# OpticalBoardRev1.net
KiCad netlist of a schematic drawn in EAGLE
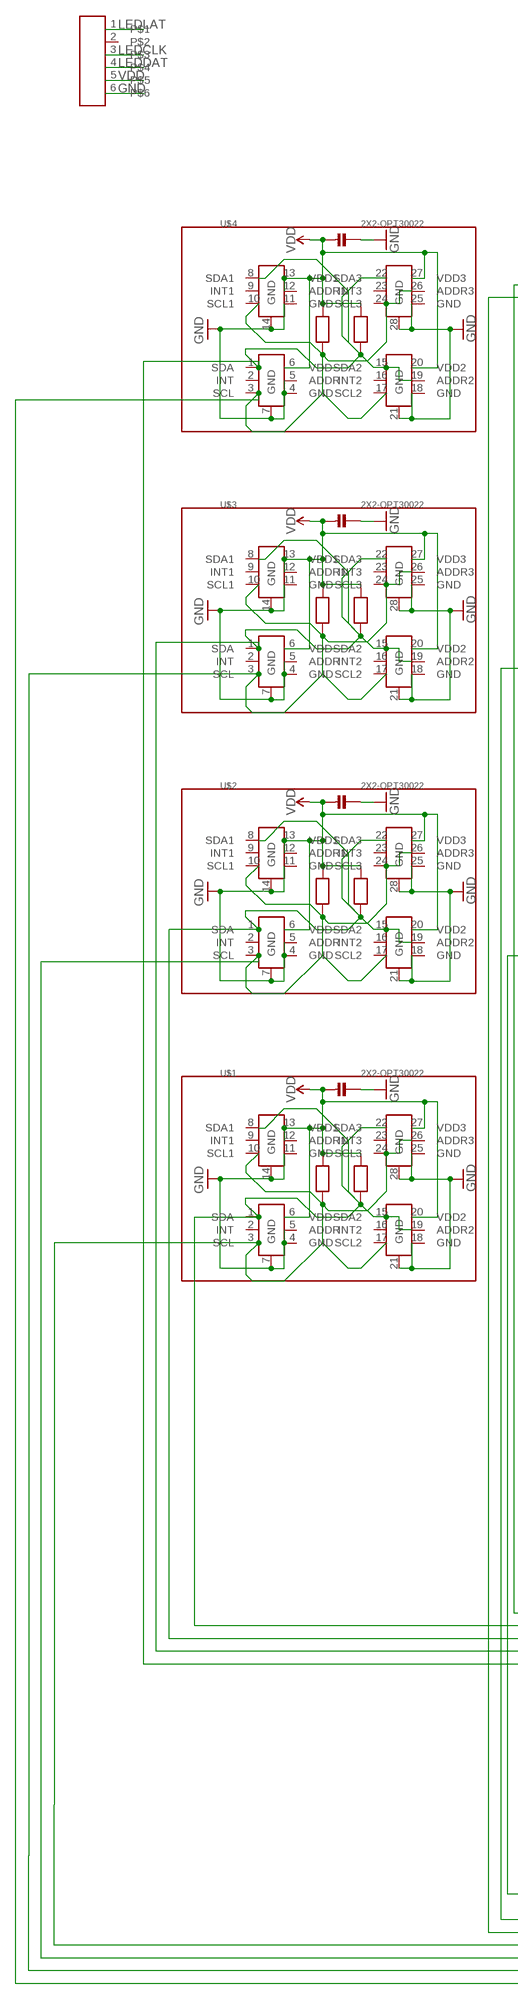
[diagram p0: schematic, sheet 1, part 1 of 2]
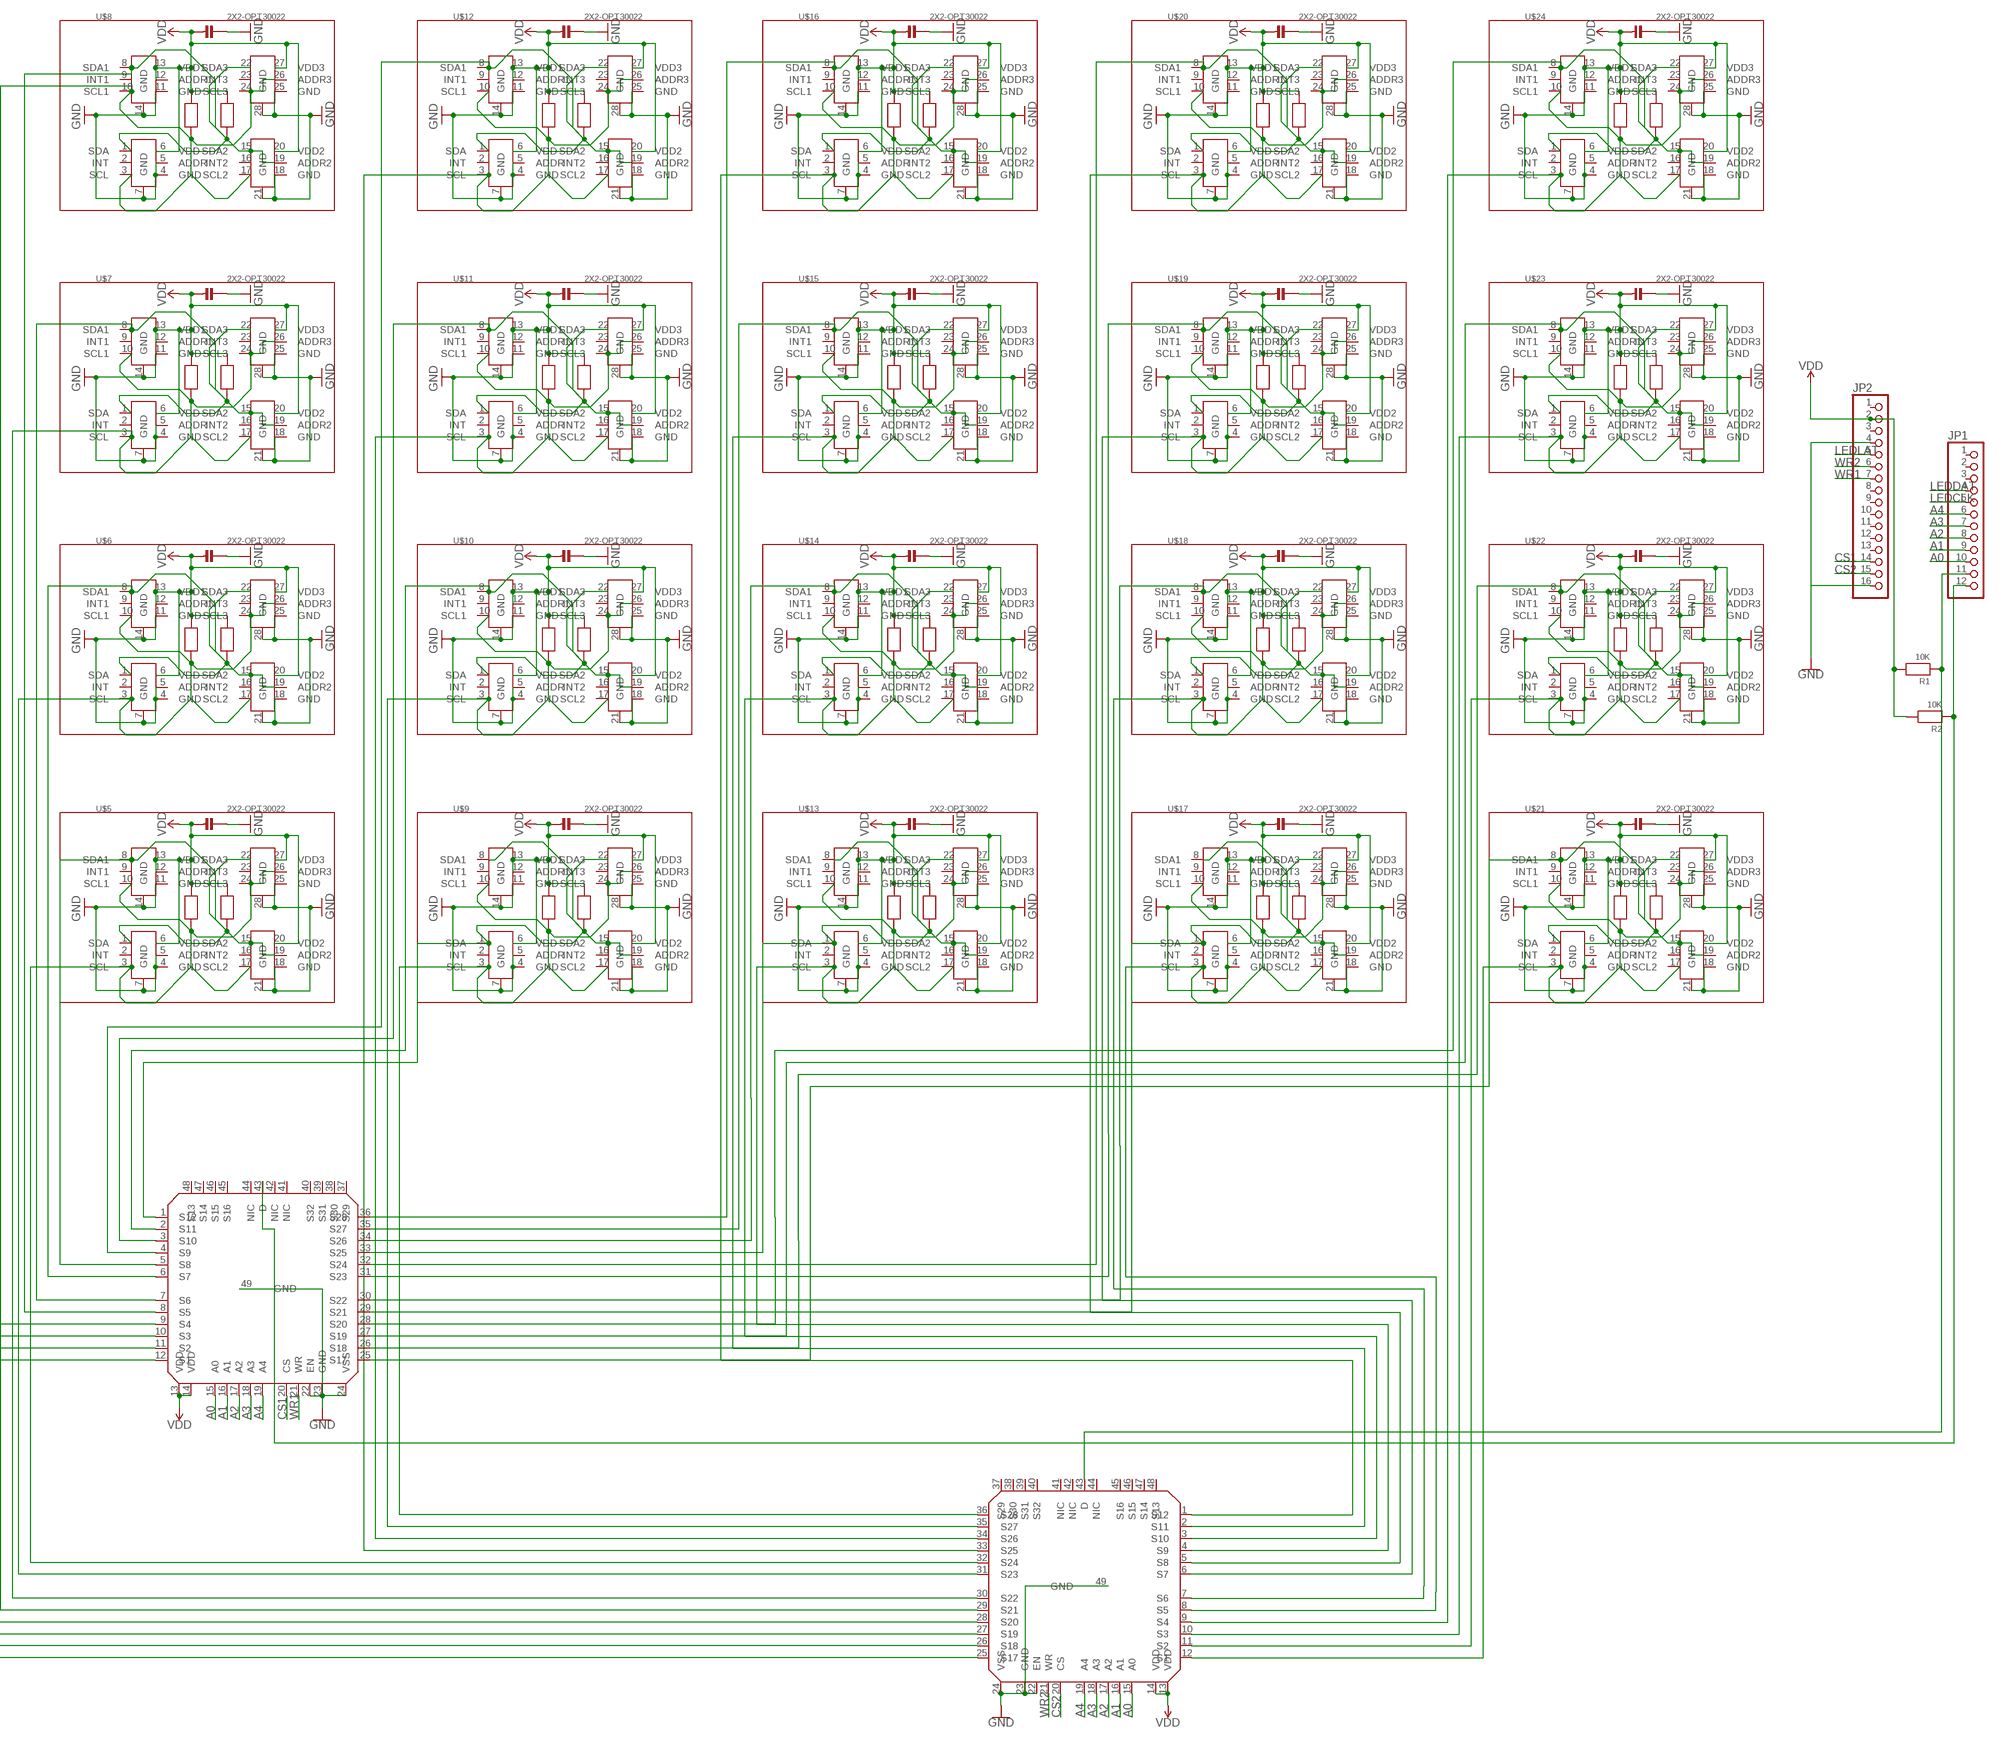
[diagram p1: schematic, sheet 1, part 2 of 2]

(export (version "E")
  (design (tool "Eeschema 10.0.6"))
  (components
    (comp (ref "JP1")
      (value "HEADER-1X12")
      (footprint "eagle-import:1X12_ROUND")
      (libsource (lib "eagle-import") (part "HEADER-1X12"))
    )
    (comp (ref "JP2")
      (value "HEADER-1X16ROUND")
      (footprint "eagle-import:1X16_ROUND")
      (libsource (lib "eagle-import") (part "HEADER-1X16ROUND"))
    )
    (comp (ref "R1")
      (value "10K")
      (footprint "eagle-import:_0805")
      (libsource (lib "eagle-import") (part "RESISTOR_0805"))
    )
    (comp (ref "R2")
      (value "10K")
      (footprint "eagle-import:_0805")
      (libsource (lib "eagle-import") (part "RESISTOR_0805"))
    )
    (comp (ref "U$1")
      (value "2X2-OPT30022")
      (footprint "eagle-import:2X2-OPT3002-2")
      (libsource (lib "eagle-import") (part "2X2-OPT30022"))
    )
    (comp (ref "U$2")
      (value "2X2-OPT30022")
      (footprint "eagle-import:2X2-OPT3002-2")
      (libsource (lib "eagle-import") (part "2X2-OPT30022"))
    )
    (comp (ref "U$3")
      (value "2X2-OPT30022")
      (footprint "eagle-import:2X2-OPT3002-2")
      (libsource (lib "eagle-import") (part "2X2-OPT30022"))
    )
    (comp (ref "U$4")
      (value "2X2-OPT30022")
      (footprint "eagle-import:2X2-OPT3002-2")
      (libsource (lib "eagle-import") (part "2X2-OPT30022"))
    )
    (comp (ref "U$5")
      (value "2X2-OPT30022")
      (footprint "eagle-import:2X2-OPT3002-2")
      (libsource (lib "eagle-import") (part "2X2-OPT30022"))
    )
    (comp (ref "U$6")
      (value "2X2-OPT30022")
      (footprint "eagle-import:2X2-OPT3002-2")
      (libsource (lib "eagle-import") (part "2X2-OPT30022"))
    )
    (comp (ref "U$7")
      (value "2X2-OPT30022")
      (footprint "eagle-import:2X2-OPT3002-2")
      (libsource (lib "eagle-import") (part "2X2-OPT30022"))
    )
    (comp (ref "U$8")
      (value "2X2-OPT30022")
      (footprint "eagle-import:2X2-OPT3002-2")
      (libsource (lib "eagle-import") (part "2X2-OPT30022"))
    )
    (comp (ref "U$9")
      (value "2X2-OPT30022")
      (footprint "eagle-import:2X2-OPT3002-2")
      (libsource (lib "eagle-import") (part "2X2-OPT30022"))
    )
    (comp (ref "U$10")
      (value "2X2-OPT30022")
      (footprint "eagle-import:2X2-OPT3002-2")
      (libsource (lib "eagle-import") (part "2X2-OPT30022"))
    )
    (comp (ref "U$11")
      (value "2X2-OPT30022")
      (footprint "eagle-import:2X2-OPT3002-2")
      (libsource (lib "eagle-import") (part "2X2-OPT30022"))
    )
    (comp (ref "U$12")
      (value "2X2-OPT30022")
      (footprint "eagle-import:2X2-OPT3002-2")
      (libsource (lib "eagle-import") (part "2X2-OPT30022"))
    )
    (comp (ref "U$13")
      (value "2X2-OPT30022")
      (footprint "eagle-import:2X2-OPT3002-2")
      (libsource (lib "eagle-import") (part "2X2-OPT30022"))
    )
    (comp (ref "U$14")
      (value "2X2-OPT30022")
      (footprint "eagle-import:2X2-OPT3002-2")
      (libsource (lib "eagle-import") (part "2X2-OPT30022"))
    )
    (comp (ref "U$15")
      (value "2X2-OPT30022")
      (footprint "eagle-import:2X2-OPT3002-2")
      (libsource (lib "eagle-import") (part "2X2-OPT30022"))
    )
    (comp (ref "U$16")
      (value "2X2-OPT30022")
      (footprint "eagle-import:2X2-OPT3002-2")
      (libsource (lib "eagle-import") (part "2X2-OPT30022"))
    )
    (comp (ref "U$17")
      (value "2X2-OPT30022")
      (footprint "eagle-import:2X2-OPT3002-2")
      (libsource (lib "eagle-import") (part "2X2-OPT30022"))
    )
    (comp (ref "U$18")
      (value "2X2-OPT30022")
      (footprint "eagle-import:2X2-OPT3002-2")
      (libsource (lib "eagle-import") (part "2X2-OPT30022"))
    )
    (comp (ref "U$19")
      (value "2X2-OPT30022")
      (footprint "eagle-import:2X2-OPT3002-2")
      (libsource (lib "eagle-import") (part "2X2-OPT30022"))
    )
    (comp (ref "U$20")
      (value "2X2-OPT30022")
      (footprint "eagle-import:2X2-OPT3002-2")
      (libsource (lib "eagle-import") (part "2X2-OPT30022"))
    )
    (comp (ref "U$21")
      (value "2X2-OPT30022")
      (footprint "eagle-import:2X2-OPT3002-2")
      (libsource (lib "eagle-import") (part "2X2-OPT30022"))
    )
    (comp (ref "U$22")
      (value "2X2-OPT30022")
      (footprint "eagle-import:2X2-OPT3002-2")
      (libsource (lib "eagle-import") (part "2X2-OPT30022"))
    )
    (comp (ref "U$23")
      (value "2X2-OPT30022")
      (footprint "eagle-import:2X2-OPT3002-2")
      (libsource (lib "eagle-import") (part "2X2-OPT30022"))
    )
    (comp (ref "U$24")
      (value "2X2-OPT30022")
      (footprint "eagle-import:2X2-OPT3002-2")
      (libsource (lib "eagle-import") (part "2X2-OPT30022"))
    )
    (comp (ref "U$25")
      (value "CONNECTOR_6PIN")
      (footprint "eagle-import:CONNECTOR_6PIN")
      (libsource (lib "eagle-import") (part "CONNECTOR_6PIN"))
    )
    (comp (ref "U$26")
      (value "32MUXTOP")
      (footprint "eagle-import:32MUX")
      (libsource (lib "eagle-import") (part "32MUXTOP"))
    )
    (comp (ref "U$27")
      (value "32MUXBOT")
      (footprint "eagle-import:32MUX_BOT")
      (libsource (lib "eagle-import") (part "32MUXBOT"))
    )
  )
  (nets
    (net (code "1") (name "/A0") (class "Default")
      (node (ref "JP1") (pin "10") (pinfunction "10_10") (pintype "passive"))
      (node (ref "U$26") (pin "15") (pinfunction "A0_15") (pintype "bidirectional"))
      (node (ref "U$27") (pin "15") (pinfunction "A0_15") (pintype "bidirectional"))
    )
    (net (code "2") (name "/A1") (class "Default")
      (node (ref "JP1") (pin "9") (pinfunction "9_9") (pintype "passive"))
      (node (ref "U$26") (pin "16") (pinfunction "A1_16") (pintype "bidirectional"))
      (node (ref "U$27") (pin "16") (pinfunction "A1_16") (pintype "bidirectional"))
    )
    (net (code "3") (name "/A2") (class "Default")
      (node (ref "JP1") (pin "8") (pinfunction "8_8") (pintype "passive"))
      (node (ref "U$26") (pin "17") (pinfunction "A2_17") (pintype "bidirectional"))
      (node (ref "U$27") (pin "17") (pinfunction "A2_17") (pintype "bidirectional"))
    )
    (net (code "4") (name "/A3") (class "Default")
      (node (ref "JP1") (pin "7") (pinfunction "7_7") (pintype "passive"))
      (node (ref "U$26") (pin "18") (pinfunction "A3_18") (pintype "bidirectional"))
      (node (ref "U$27") (pin "18") (pinfunction "A3_18") (pintype "bidirectional"))
    )
    (net (code "5") (name "/A4") (class "Default")
      (node (ref "JP1") (pin "6") (pinfunction "6_6") (pintype "passive"))
      (node (ref "U$26") (pin "19") (pinfunction "A4_19") (pintype "bidirectional"))
      (node (ref "U$27") (pin "19") (pinfunction "A4_19") (pintype "bidirectional"))
    )
    (net (code "6") (name "/CS1") (class "Default")
      (node (ref "JP2") (pin "14") (pinfunction "14_14") (pintype "passive"))
      (node (ref "U$26") (pin "20") (pinfunction "CS_20") (pintype "bidirectional"))
    )
    (net (code "7") (name "/CS2") (class "Default")
      (node (ref "JP2") (pin "15") (pinfunction "15_15") (pintype "passive"))
      (node (ref "U$27") (pin "20") (pinfunction "CS_20") (pintype "bidirectional"))
    )
    (net (code "8") (name "/LEDCLK") (class "Default")
      (node (ref "JP1") (pin "5") (pinfunction "5_5") (pintype "passive"))
      (node (ref "U$25") (pin "3") (pinfunction "P$3_3") (pintype "bidirectional"))
    )
    (net (code "9") (name "/LEDDAT") (class "Default")
      (node (ref "JP1") (pin "4") (pinfunction "4_4") (pintype "passive"))
      (node (ref "U$25") (pin "4") (pinfunction "P$4_4") (pintype "bidirectional"))
    )
    (net (code "10") (name "/LEDLAT") (class "Default")
      (node (ref "JP2") (pin "5") (pinfunction "5_5") (pintype "passive"))
      (node (ref "U$25") (pin "1") (pinfunction "P$1_1") (pintype "bidirectional"))
    )
    (net (code "11") (name "/WR1") (class "Default")
      (node (ref "JP2") (pin "7") (pinfunction "7_7") (pintype "passive"))
      (node (ref "U$26") (pin "21") (pinfunction "WR_21") (pintype "bidirectional"))
    )
    (net (code "12") (name "/WR2") (class "Default")
      (node (ref "JP2") (pin "6") (pinfunction "6_6") (pintype "passive"))
      (node (ref "U$27") (pin "21") (pinfunction "WR_21") (pintype "bidirectional"))
    )
    (net (code "13") (name "GND") (class "Default")
      (node (ref "JP2") (pin "16") (pinfunction "16_16") (pintype "passive"))
      (node (ref "JP2") (pin "4") (pinfunction "4_4") (pintype "passive"))
      (node (ref "U$1") (pin "11") (pinfunction "GND_11") (pintype "bidirectional"))
      (node (ref "U$1") (pin "14") (pinfunction "GND_14") (pintype "bidirectional"))
      (node (ref "U$1") (pin "18") (pinfunction "GND_18") (pintype "bidirectional"))
      (node (ref "U$1") (pin "21") (pinfunction "GND_21") (pintype "bidirectional"))
      (node (ref "U$1") (pin "25") (pinfunction "GND_25") (pintype "bidirectional"))
      (node (ref "U$1") (pin "28") (pinfunction "GND_28") (pintype "bidirectional"))
      (node (ref "U$1") (pin "30") (pinfunction "GND_30") (pintype "passive"))
      (node (ref "U$1") (pin "4") (pinfunction "GND_4") (pintype "bidirectional"))
      (node (ref "U$1") (pin "5") (pinfunction "ADDR_5") (pintype "bidirectional"))
      (node (ref "U$1") (pin "7") (pinfunction "GND_7") (pintype "bidirectional"))
      (node (ref "U$10") (pin "11") (pinfunction "GND_11") (pintype "bidirectional"))
      (node (ref "U$10") (pin "14") (pinfunction "GND_14") (pintype "bidirectional"))
      (node (ref "U$10") (pin "18") (pinfunction "GND_18") (pintype "bidirectional"))
      (node (ref "U$10") (pin "21") (pinfunction "GND_21") (pintype "bidirectional"))
      (node (ref "U$10") (pin "25") (pinfunction "GND_25") (pintype "bidirectional"))
      (node (ref "U$10") (pin "28") (pinfunction "GND_28") (pintype "bidirectional"))
      (node (ref "U$10") (pin "30") (pinfunction "GND_30") (pintype "passive"))
      (node (ref "U$10") (pin "4") (pinfunction "GND_4") (pintype "bidirectional"))
      (node (ref "U$10") (pin "5") (pinfunction "ADDR_5") (pintype "bidirectional"))
      (node (ref "U$10") (pin "7") (pinfunction "GND_7") (pintype "bidirectional"))
      (node (ref "U$11") (pin "11") (pinfunction "GND_11") (pintype "bidirectional"))
      (node (ref "U$11") (pin "14") (pinfunction "GND_14") (pintype "bidirectional"))
      (node (ref "U$11") (pin "18") (pinfunction "GND_18") (pintype "bidirectional"))
      (node (ref "U$11") (pin "21") (pinfunction "GND_21") (pintype "bidirectional"))
      (node (ref "U$11") (pin "25") (pinfunction "GND_25") (pintype "bidirectional"))
      (node (ref "U$11") (pin "28") (pinfunction "GND_28") (pintype "bidirectional"))
      (node (ref "U$11") (pin "30") (pinfunction "GND_30") (pintype "passive"))
      (node (ref "U$11") (pin "4") (pinfunction "GND_4") (pintype "bidirectional"))
      (node (ref "U$11") (pin "5") (pinfunction "ADDR_5") (pintype "bidirectional"))
      (node (ref "U$11") (pin "7") (pinfunction "GND_7") (pintype "bidirectional"))
      (node (ref "U$12") (pin "11") (pinfunction "GND_11") (pintype "bidirectional"))
      (node (ref "U$12") (pin "14") (pinfunction "GND_14") (pintype "bidirectional"))
      (node (ref "U$12") (pin "18") (pinfunction "GND_18") (pintype "bidirectional"))
      (node (ref "U$12") (pin "21") (pinfunction "GND_21") (pintype "bidirectional"))
      (node (ref "U$12") (pin "25") (pinfunction "GND_25") (pintype "bidirectional"))
      (node (ref "U$12") (pin "28") (pinfunction "GND_28") (pintype "bidirectional"))
      (node (ref "U$12") (pin "30") (pinfunction "GND_30") (pintype "passive"))
      (node (ref "U$12") (pin "4") (pinfunction "GND_4") (pintype "bidirectional"))
      (node (ref "U$12") (pin "5") (pinfunction "ADDR_5") (pintype "bidirectional"))
      (node (ref "U$12") (pin "7") (pinfunction "GND_7") (pintype "bidirectional"))
      (node (ref "U$13") (pin "11") (pinfunction "GND_11") (pintype "bidirectional"))
      (node (ref "U$13") (pin "14") (pinfunction "GND_14") (pintype "bidirectional"))
      (node (ref "U$13") (pin "18") (pinfunction "GND_18") (pintype "bidirectional"))
      (node (ref "U$13") (pin "21") (pinfunction "GND_21") (pintype "bidirectional"))
      (node (ref "U$13") (pin "25") (pinfunction "GND_25") (pintype "bidirectional"))
      (node (ref "U$13") (pin "28") (pinfunction "GND_28") (pintype "bidirectional"))
      (node (ref "U$13") (pin "30") (pinfunction "GND_30") (pintype "passive"))
      (node (ref "U$13") (pin "4") (pinfunction "GND_4") (pintype "bidirectional"))
      (node (ref "U$13") (pin "5") (pinfunction "ADDR_5") (pintype "bidirectional"))
      (node (ref "U$13") (pin "7") (pinfunction "GND_7") (pintype "bidirectional"))
      (node (ref "U$14") (pin "11") (pinfunction "GND_11") (pintype "bidirectional"))
      (node (ref "U$14") (pin "14") (pinfunction "GND_14") (pintype "bidirectional"))
      (node (ref "U$14") (pin "18") (pinfunction "GND_18") (pintype "bidirectional"))
      (node (ref "U$14") (pin "21") (pinfunction "GND_21") (pintype "bidirectional"))
      (node (ref "U$14") (pin "25") (pinfunction "GND_25") (pintype "bidirectional"))
      (node (ref "U$14") (pin "28") (pinfunction "GND_28") (pintype "bidirectional"))
      (node (ref "U$14") (pin "30") (pinfunction "GND_30") (pintype "passive"))
      (node (ref "U$14") (pin "4") (pinfunction "GND_4") (pintype "bidirectional"))
      (node (ref "U$14") (pin "5") (pinfunction "ADDR_5") (pintype "bidirectional"))
      (node (ref "U$14") (pin "7") (pinfunction "GND_7") (pintype "bidirectional"))
      (node (ref "U$15") (pin "11") (pinfunction "GND_11") (pintype "bidirectional"))
      (node (ref "U$15") (pin "14") (pinfunction "GND_14") (pintype "bidirectional"))
      (node (ref "U$15") (pin "18") (pinfunction "GND_18") (pintype "bidirectional"))
      (node (ref "U$15") (pin "21") (pinfunction "GND_21") (pintype "bidirectional"))
      (node (ref "U$15") (pin "25") (pinfunction "GND_25") (pintype "bidirectional"))
      (node (ref "U$15") (pin "28") (pinfunction "GND_28") (pintype "bidirectional"))
      (node (ref "U$15") (pin "30") (pinfunction "GND_30") (pintype "passive"))
      (node (ref "U$15") (pin "4") (pinfunction "GND_4") (pintype "bidirectional"))
      (node (ref "U$15") (pin "5") (pinfunction "ADDR_5") (pintype "bidirectional"))
      (node (ref "U$15") (pin "7") (pinfunction "GND_7") (pintype "bidirectional"))
      (node (ref "U$16") (pin "11") (pinfunction "GND_11") (pintype "bidirectional"))
      (node (ref "U$16") (pin "14") (pinfunction "GND_14") (pintype "bidirectional"))
      (node (ref "U$16") (pin "18") (pinfunction "GND_18") (pintype "bidirectional"))
      (node (ref "U$16") (pin "21") (pinfunction "GND_21") (pintype "bidirectional"))
      (node (ref "U$16") (pin "25") (pinfunction "GND_25") (pintype "bidirectional"))
      (node (ref "U$16") (pin "28") (pinfunction "GND_28") (pintype "bidirectional"))
      (node (ref "U$16") (pin "30") (pinfunction "GND_30") (pintype "passive"))
      (node (ref "U$16") (pin "4") (pinfunction "GND_4") (pintype "bidirectional"))
      (node (ref "U$16") (pin "5") (pinfunction "ADDR_5") (pintype "bidirectional"))
      (node (ref "U$16") (pin "7") (pinfunction "GND_7") (pintype "bidirectional"))
      (node (ref "U$17") (pin "11") (pinfunction "GND_11") (pintype "bidirectional"))
      (node (ref "U$17") (pin "14") (pinfunction "GND_14") (pintype "bidirectional"))
      (node (ref "U$17") (pin "18") (pinfunction "GND_18") (pintype "bidirectional"))
      (node (ref "U$17") (pin "21") (pinfunction "GND_21") (pintype "bidirectional"))
      (node (ref "U$17") (pin "25") (pinfunction "GND_25") (pintype "bidirectional"))
      (node (ref "U$17") (pin "28") (pinfunction "GND_28") (pintype "bidirectional"))
      (node (ref "U$17") (pin "30") (pinfunction "GND_30") (pintype "passive"))
      (node (ref "U$17") (pin "4") (pinfunction "GND_4") (pintype "bidirectional"))
      (node (ref "U$17") (pin "5") (pinfunction "ADDR_5") (pintype "bidirectional"))
      (node (ref "U$17") (pin "7") (pinfunction "GND_7") (pintype "bidirectional"))
      (node (ref "U$18") (pin "11") (pinfunction "GND_11") (pintype "bidirectional"))
      (node (ref "U$18") (pin "14") (pinfunction "GND_14") (pintype "bidirectional"))
      (node (ref "U$18") (pin "18") (pinfunction "GND_18") (pintype "bidirectional"))
      (node (ref "U$18") (pin "21") (pinfunction "GND_21") (pintype "bidirectional"))
      (node (ref "U$18") (pin "25") (pinfunction "GND_25") (pintype "bidirectional"))
      (node (ref "U$18") (pin "28") (pinfunction "GND_28") (pintype "bidirectional"))
      (node (ref "U$18") (pin "30") (pinfunction "GND_30") (pintype "passive"))
      (node (ref "U$18") (pin "4") (pinfunction "GND_4") (pintype "bidirectional"))
      (node (ref "U$18") (pin "5") (pinfunction "ADDR_5") (pintype "bidirectional"))
      (node (ref "U$18") (pin "7") (pinfunction "GND_7") (pintype "bidirectional"))
      (node (ref "U$19") (pin "11") (pinfunction "GND_11") (pintype "bidirectional"))
      (node (ref "U$19") (pin "14") (pinfunction "GND_14") (pintype "bidirectional"))
      (node (ref "U$19") (pin "18") (pinfunction "GND_18") (pintype "bidirectional"))
      (node (ref "U$19") (pin "21") (pinfunction "GND_21") (pintype "bidirectional"))
      (node (ref "U$19") (pin "25") (pinfunction "GND_25") (pintype "bidirectional"))
      (node (ref "U$19") (pin "28") (pinfunction "GND_28") (pintype "bidirectional"))
      (node (ref "U$19") (pin "30") (pinfunction "GND_30") (pintype "passive"))
      (node (ref "U$19") (pin "4") (pinfunction "GND_4") (pintype "bidirectional"))
      (node (ref "U$19") (pin "5") (pinfunction "ADDR_5") (pintype "bidirectional"))
      (node (ref "U$19") (pin "7") (pinfunction "GND_7") (pintype "bidirectional"))
      (node (ref "U$2") (pin "11") (pinfunction "GND_11") (pintype "bidirectional"))
      (node (ref "U$2") (pin "14") (pinfunction "GND_14") (pintype "bidirectional"))
      (node (ref "U$2") (pin "18") (pinfunction "GND_18") (pintype "bidirectional"))
      (node (ref "U$2") (pin "21") (pinfunction "GND_21") (pintype "bidirectional"))
      (node (ref "U$2") (pin "25") (pinfunction "GND_25") (pintype "bidirectional"))
      (node (ref "U$2") (pin "28") (pinfunction "GND_28") (pintype "bidirectional"))
      (node (ref "U$2") (pin "30") (pinfunction "GND_30") (pintype "passive"))
      (node (ref "U$2") (pin "4") (pinfunction "GND_4") (pintype "bidirectional"))
      (node (ref "U$2") (pin "5") (pinfunction "ADDR_5") (pintype "bidirectional"))
      (node (ref "U$2") (pin "7") (pinfunction "GND_7") (pintype "bidirectional"))
      (node (ref "U$20") (pin "11") (pinfunction "GND_11") (pintype "bidirectional"))
      (node (ref "U$20") (pin "14") (pinfunction "GND_14") (pintype "bidirectional"))
      (node (ref "U$20") (pin "18") (pinfunction "GND_18") (pintype "bidirectional"))
      (node (ref "U$20") (pin "21") (pinfunction "GND_21") (pintype "bidirectional"))
      (node (ref "U$20") (pin "25") (pinfunction "GND_25") (pintype "bidirectional"))
      (node (ref "U$20") (pin "28") (pinfunction "GND_28") (pintype "bidirectional"))
      (node (ref "U$20") (pin "30") (pinfunction "GND_30") (pintype "passive"))
      (node (ref "U$20") (pin "4") (pinfunction "GND_4") (pintype "bidirectional"))
      (node (ref "U$20") (pin "5") (pinfunction "ADDR_5") (pintype "bidirectional"))
      (node (ref "U$20") (pin "7") (pinfunction "GND_7") (pintype "bidirectional"))
      (node (ref "U$21") (pin "11") (pinfunction "GND_11") (pintype "bidirectional"))
      (node (ref "U$21") (pin "14") (pinfunction "GND_14") (pintype "bidirectional"))
      (node (ref "U$21") (pin "18") (pinfunction "GND_18") (pintype "bidirectional"))
      (node (ref "U$21") (pin "21") (pinfunction "GND_21") (pintype "bidirectional"))
      (node (ref "U$21") (pin "25") (pinfunction "GND_25") (pintype "bidirectional"))
      (node (ref "U$21") (pin "28") (pinfunction "GND_28") (pintype "bidirectional"))
      (node (ref "U$21") (pin "30") (pinfunction "GND_30") (pintype "passive"))
      (node (ref "U$21") (pin "4") (pinfunction "GND_4") (pintype "bidirectional"))
      (node (ref "U$21") (pin "5") (pinfunction "ADDR_5") (pintype "bidirectional"))
      (node (ref "U$21") (pin "7") (pinfunction "GND_7") (pintype "bidirectional"))
      (node (ref "U$22") (pin "11") (pinfunction "GND_11") (pintype "bidirectional"))
      (node (ref "U$22") (pin "14") (pinfunction "GND_14") (pintype "bidirectional"))
      (node (ref "U$22") (pin "18") (pinfunction "GND_18") (pintype "bidirectional"))
      (node (ref "U$22") (pin "21") (pinfunction "GND_21") (pintype "bidirectional"))
      (node (ref "U$22") (pin "25") (pinfunction "GND_25") (pintype "bidirectional"))
      (node (ref "U$22") (pin "28") (pinfunction "GND_28") (pintype "bidirectional"))
      (node (ref "U$22") (pin "30") (pinfunction "GND_30") (pintype "passive"))
      (node (ref "U$22") (pin "4") (pinfunction "GND_4") (pintype "bidirectional"))
      (node (ref "U$22") (pin "5") (pinfunction "ADDR_5") (pintype "bidirectional"))
      (node (ref "U$22") (pin "7") (pinfunction "GND_7") (pintype "bidirectional"))
      (node (ref "U$23") (pin "11") (pinfunction "GND_11") (pintype "bidirectional"))
      (node (ref "U$23") (pin "14") (pinfunction "GND_14") (pintype "bidirectional"))
      (node (ref "U$23") (pin "18") (pinfunction "GND_18") (pintype "bidirectional"))
      (node (ref "U$23") (pin "21") (pinfunction "GND_21") (pintype "bidirectional"))
      (node (ref "U$23") (pin "25") (pinfunction "GND_25") (pintype "bidirectional"))
      (node (ref "U$23") (pin "28") (pinfunction "GND_28") (pintype "bidirectional"))
      (node (ref "U$23") (pin "30") (pinfunction "GND_30") (pintype "passive"))
      (node (ref "U$23") (pin "4") (pinfunction "GND_4") (pintype "bidirectional"))
      (node (ref "U$23") (pin "5") (pinfunction "ADDR_5") (pintype "bidirectional"))
      (node (ref "U$23") (pin "7") (pinfunction "GND_7") (pintype "bidirectional"))
      (node (ref "U$24") (pin "11") (pinfunction "GND_11") (pintype "bidirectional"))
      (node (ref "U$24") (pin "14") (pinfunction "GND_14") (pintype "bidirectional"))
      (node (ref "U$24") (pin "18") (pinfunction "GND_18") (pintype "bidirectional"))
      (node (ref "U$24") (pin "21") (pinfunction "GND_21") (pintype "bidirectional"))
      (node (ref "U$24") (pin "25") (pinfunction "GND_25") (pintype "bidirectional"))
      (node (ref "U$24") (pin "28") (pinfunction "GND_28") (pintype "bidirectional"))
      (node (ref "U$24") (pin "30") (pinfunction "GND_30") (pintype "passive"))
      (node (ref "U$24") (pin "4") (pinfunction "GND_4") (pintype "bidirectional"))
      (node (ref "U$24") (pin "5") (pinfunction "ADDR_5") (pintype "bidirectional"))
      (node (ref "U$24") (pin "7") (pinfunction "GND_7") (pintype "bidirectional"))
      (node (ref "U$25") (pin "6") (pinfunction "P$6_6") (pintype "bidirectional"))
      (node (ref "U$26") (pin "22") (pinfunction "EN_22") (pintype "bidirectional"))
      (node (ref "U$26") (pin "23") (pinfunction "GND_23") (pintype "bidirectional"))
      (node (ref "U$26") (pin "24") (pinfunction "VSS_24") (pintype "bidirectional"))
      (node (ref "U$26") (pin "49") (pinfunction "GND_49") (pintype "bidirectional"))
      (node (ref "U$27") (pin "22") (pinfunction "EN_22") (pintype "bidirectional"))
      (node (ref "U$27") (pin "23") (pinfunction "GND_23") (pintype "bidirectional"))
      (node (ref "U$27") (pin "24") (pinfunction "VSS_24") (pintype "bidirectional"))
      (node (ref "U$27") (pin "49") (pinfunction "GND_49") (pintype "bidirectional"))
      (node (ref "U$3") (pin "11") (pinfunction "GND_11") (pintype "bidirectional"))
      (node (ref "U$3") (pin "14") (pinfunction "GND_14") (pintype "bidirectional"))
      (node (ref "U$3") (pin "18") (pinfunction "GND_18") (pintype "bidirectional"))
      (node (ref "U$3") (pin "21") (pinfunction "GND_21") (pintype "bidirectional"))
      (node (ref "U$3") (pin "25") (pinfunction "GND_25") (pintype "bidirectional"))
      (node (ref "U$3") (pin "28") (pinfunction "GND_28") (pintype "bidirectional"))
      (node (ref "U$3") (pin "30") (pinfunction "GND_30") (pintype "passive"))
      (node (ref "U$3") (pin "4") (pinfunction "GND_4") (pintype "bidirectional"))
      (node (ref "U$3") (pin "5") (pinfunction "ADDR_5") (pintype "bidirectional"))
      (node (ref "U$3") (pin "7") (pinfunction "GND_7") (pintype "bidirectional"))
      (node (ref "U$4") (pin "11") (pinfunction "GND_11") (pintype "bidirectional"))
      (node (ref "U$4") (pin "14") (pinfunction "GND_14") (pintype "bidirectional"))
      (node (ref "U$4") (pin "18") (pinfunction "GND_18") (pintype "bidirectional"))
      (node (ref "U$4") (pin "21") (pinfunction "GND_21") (pintype "bidirectional"))
      (node (ref "U$4") (pin "25") (pinfunction "GND_25") (pintype "bidirectional"))
      (node (ref "U$4") (pin "28") (pinfunction "GND_28") (pintype "bidirectional"))
      (node (ref "U$4") (pin "30") (pinfunction "GND_30") (pintype "passive"))
      (node (ref "U$4") (pin "4") (pinfunction "GND_4") (pintype "bidirectional"))
      (node (ref "U$4") (pin "5") (pinfunction "ADDR_5") (pintype "bidirectional"))
      (node (ref "U$4") (pin "7") (pinfunction "GND_7") (pintype "bidirectional"))
      (node (ref "U$5") (pin "11") (pinfunction "GND_11") (pintype "bidirectional"))
      (node (ref "U$5") (pin "14") (pinfunction "GND_14") (pintype "bidirectional"))
      (node (ref "U$5") (pin "18") (pinfunction "GND_18") (pintype "bidirectional"))
      (node (ref "U$5") (pin "21") (pinfunction "GND_21") (pintype "bidirectional"))
      (node (ref "U$5") (pin "25") (pinfunction "GND_25") (pintype "bidirectional"))
      (node (ref "U$5") (pin "28") (pinfunction "GND_28") (pintype "bidirectional"))
      (node (ref "U$5") (pin "30") (pinfunction "GND_30") (pintype "passive"))
      (node (ref "U$5") (pin "4") (pinfunction "GND_4") (pintype "bidirectional"))
      (node (ref "U$5") (pin "5") (pinfunction "ADDR_5") (pintype "bidirectional"))
      (node (ref "U$5") (pin "7") (pinfunction "GND_7") (pintype "bidirectional"))
      (node (ref "U$6") (pin "11") (pinfunction "GND_11") (pintype "bidirectional"))
      (node (ref "U$6") (pin "14") (pinfunction "GND_14") (pintype "bidirectional"))
      (node (ref "U$6") (pin "18") (pinfunction "GND_18") (pintype "bidirectional"))
      (node (ref "U$6") (pin "21") (pinfunction "GND_21") (pintype "bidirectional"))
      (node (ref "U$6") (pin "25") (pinfunction "GND_25") (pintype "bidirectional"))
      (node (ref "U$6") (pin "28") (pinfunction "GND_28") (pintype "bidirectional"))
      (node (ref "U$6") (pin "30") (pinfunction "GND_30") (pintype "passive"))
      (node (ref "U$6") (pin "4") (pinfunction "GND_4") (pintype "bidirectional"))
      (node (ref "U$6") (pin "5") (pinfunction "ADDR_5") (pintype "bidirectional"))
      (node (ref "U$6") (pin "7") (pinfunction "GND_7") (pintype "bidirectional"))
      (node (ref "U$7") (pin "11") (pinfunction "GND_11") (pintype "bidirectional"))
      (node (ref "U$7") (pin "14") (pinfunction "GND_14") (pintype "bidirectional"))
      (node (ref "U$7") (pin "18") (pinfunction "GND_18") (pintype "bidirectional"))
      (node (ref "U$7") (pin "21") (pinfunction "GND_21") (pintype "bidirectional"))
      (node (ref "U$7") (pin "25") (pinfunction "GND_25") (pintype "bidirectional"))
      (node (ref "U$7") (pin "28") (pinfunction "GND_28") (pintype "bidirectional"))
      (node (ref "U$7") (pin "30") (pinfunction "GND_30") (pintype "passive"))
      (node (ref "U$7") (pin "4") (pinfunction "GND_4") (pintype "bidirectional"))
      (node (ref "U$7") (pin "5") (pinfunction "ADDR_5") (pintype "bidirectional"))
      (node (ref "U$7") (pin "7") (pinfunction "GND_7") (pintype "bidirectional"))
      (node (ref "U$8") (pin "11") (pinfunction "GND_11") (pintype "bidirectional"))
      (node (ref "U$8") (pin "14") (pinfunction "GND_14") (pintype "bidirectional"))
      (node (ref "U$8") (pin "18") (pinfunction "GND_18") (pintype "bidirectional"))
      (node (ref "U$8") (pin "21") (pinfunction "GND_21") (pintype "bidirectional"))
      (node (ref "U$8") (pin "25") (pinfunction "GND_25") (pintype "bidirectional"))
      (node (ref "U$8") (pin "28") (pinfunction "GND_28") (pintype "bidirectional"))
      (node (ref "U$8") (pin "30") (pinfunction "GND_30") (pintype "passive"))
      (node (ref "U$8") (pin "4") (pinfunction "GND_4") (pintype "bidirectional"))
      (node (ref "U$8") (pin "5") (pinfunction "ADDR_5") (pintype "bidirectional"))
      (node (ref "U$8") (pin "7") (pinfunction "GND_7") (pintype "bidirectional"))
      (node (ref "U$9") (pin "11") (pinfunction "GND_11") (pintype "bidirectional"))
      (node (ref "U$9") (pin "14") (pinfunction "GND_14") (pintype "bidirectional"))
      (node (ref "U$9") (pin "18") (pinfunction "GND_18") (pintype "bidirectional"))
      (node (ref "U$9") (pin "21") (pinfunction "GND_21") (pintype "bidirectional"))
      (node (ref "U$9") (pin "25") (pinfunction "GND_25") (pintype "bidirectional"))
      (node (ref "U$9") (pin "28") (pinfunction "GND_28") (pintype "bidirectional"))
      (node (ref "U$9") (pin "30") (pinfunction "GND_30") (pintype "passive"))
      (node (ref "U$9") (pin "4") (pinfunction "GND_4") (pintype "bidirectional"))
      (node (ref "U$9") (pin "5") (pinfunction "ADDR_5") (pintype "bidirectional"))
      (node (ref "U$9") (pin "7") (pinfunction "GND_7") (pintype "bidirectional"))
    )
    (net (code "14") (name "Net-(U$1-ADDR2)") (class "Default")
      (node (ref "U$1") (pin "1") (pinfunction "SDA_1") (pintype "bidirectional"))
      (node (ref "U$1") (pin "15") (pinfunction "SDA2_15") (pintype "bidirectional"))
      (node (ref "U$1") (pin "19") (pinfunction "ADDR2_19") (pintype "bidirectional"))
      (node (ref "U$1") (pin "22") (pinfunction "SDA3_22") (pintype "bidirectional"))
      (node (ref "U$1") (pin "33") (pinfunction "R2+_33") (pintype "passive"))
      (node (ref "U$1") (pin "8") (pinfunction "SDA1_8") (pintype "bidirectional"))
      (node (ref "U$26") (pin "9") (pinfunction "S4_9") (pintype "bidirectional"))
    )
    (net (code "15") (name "Net-(U$1-ADDR3)") (class "Default")
      (node (ref "U$1") (pin "10") (pinfunction "SCL1_10") (pintype "bidirectional"))
      (node (ref "U$1") (pin "17") (pinfunction "SCL2_17") (pintype "bidirectional"))
      (node (ref "U$1") (pin "24") (pinfunction "SCL3_24") (pintype "bidirectional"))
      (node (ref "U$1") (pin "26") (pinfunction "ADDR3_26") (pintype "bidirectional"))
      (node (ref "U$1") (pin "3") (pinfunction "SCL_3") (pintype "bidirectional"))
      (node (ref "U$1") (pin "31") (pinfunction "R1+_31") (pintype "passive"))
      (node (ref "U$27") (pin "28") (pinfunction "S20_28") (pintype "bidirectional"))
    )
    (net (code "16") (name "Net-(U$2-ADDR2)") (class "Default")
      (node (ref "U$2") (pin "1") (pinfunction "SDA_1") (pintype "bidirectional"))
      (node (ref "U$2") (pin "15") (pinfunction "SDA2_15") (pintype "bidirectional"))
      (node (ref "U$2") (pin "19") (pinfunction "ADDR2_19") (pintype "bidirectional"))
      (node (ref "U$2") (pin "22") (pinfunction "SDA3_22") (pintype "bidirectional"))
      (node (ref "U$2") (pin "33") (pinfunction "R2+_33") (pintype "passive"))
      (node (ref "U$2") (pin "8") (pinfunction "SDA1_8") (pintype "bidirectional"))
      (node (ref "U$26") (pin "10") (pinfunction "S3_10") (pintype "bidirectional"))
    )
    (net (code "17") (name "Net-(U$2-ADDR3)") (class "Default")
      (node (ref "U$2") (pin "10") (pinfunction "SCL1_10") (pintype "bidirectional"))
      (node (ref "U$2") (pin "17") (pinfunction "SCL2_17") (pintype "bidirectional"))
      (node (ref "U$2") (pin "24") (pinfunction "SCL3_24") (pintype "bidirectional"))
      (node (ref "U$2") (pin "26") (pinfunction "ADDR3_26") (pintype "bidirectional"))
      (node (ref "U$2") (pin "3") (pinfunction "SCL_3") (pintype "bidirectional"))
      (node (ref "U$2") (pin "31") (pinfunction "R1+_31") (pintype "passive"))
      (node (ref "U$27") (pin "27") (pinfunction "S19_27") (pintype "bidirectional"))
    )
    (net (code "18") (name "Net-(U$10-ADDR2)") (class "Default")
      (node (ref "U$10") (pin "1") (pinfunction "SDA_1") (pintype "bidirectional"))
      (node (ref "U$10") (pin "15") (pinfunction "SDA2_15") (pintype "bidirectional"))
      (node (ref "U$10") (pin "19") (pinfunction "ADDR2_19") (pintype "bidirectional"))
      (node (ref "U$10") (pin "22") (pinfunction "SDA3_22") (pintype "bidirectional"))
      (node (ref "U$10") (pin "33") (pinfunction "R2+_33") (pintype "passive"))
      (node (ref "U$10") (pin "8") (pinfunction "SDA1_8") (pintype "bidirectional"))
      (node (ref "U$26") (pin "2") (pinfunction "S11_2") (pintype "bidirectional"))
    )
    (net (code "19") (name "Net-(U$10-ADDR3)") (class "Default")
      (node (ref "U$10") (pin "10") (pinfunction "SCL1_10") (pintype "bidirectional"))
      (node (ref "U$10") (pin "17") (pinfunction "SCL2_17") (pintype "bidirectional"))
      (node (ref "U$10") (pin "24") (pinfunction "SCL3_24") (pintype "bidirectional"))
      (node (ref "U$10") (pin "26") (pinfunction "ADDR3_26") (pintype "bidirectional"))
      (node (ref "U$10") (pin "3") (pinfunction "SCL_3") (pintype "bidirectional"))
      (node (ref "U$10") (pin "31") (pinfunction "R1+_31") (pintype "passive"))
      (node (ref "U$27") (pin "35") (pinfunction "S27_35") (pintype "bidirectional"))
    )
    (net (code "20") (name "Net-(U$11-ADDR2)") (class "Default")
      (node (ref "U$11") (pin "1") (pinfunction "SDA_1") (pintype "bidirectional"))
      (node (ref "U$11") (pin "15") (pinfunction "SDA2_15") (pintype "bidirectional"))
      (node (ref "U$11") (pin "19") (pinfunction "ADDR2_19") (pintype "bidirectional"))
      (node (ref "U$11") (pin "22") (pinfunction "SDA3_22") (pintype "bidirectional"))
      (node (ref "U$11") (pin "33") (pinfunction "R2+_33") (pintype "passive"))
      (node (ref "U$11") (pin "8") (pinfunction "SDA1_8") (pintype "bidirectional"))
      (node (ref "U$26") (pin "3") (pinfunction "S10_3") (pintype "bidirectional"))
    )
    (net (code "21") (name "Net-(U$11-ADDR3)") (class "Default")
      (node (ref "U$11") (pin "10") (pinfunction "SCL1_10") (pintype "bidirectional"))
      (node (ref "U$11") (pin "17") (pinfunction "SCL2_17") (pintype "bidirectional"))
      (node (ref "U$11") (pin "24") (pinfunction "SCL3_24") (pintype "bidirectional"))
      (node (ref "U$11") (pin "26") (pinfunction "ADDR3_26") (pintype "bidirectional"))
      (node (ref "U$11") (pin "3") (pinfunction "SCL_3") (pintype "bidirectional"))
      (node (ref "U$11") (pin "31") (pinfunction "R1+_31") (pintype "passive"))
      (node (ref "U$27") (pin "34") (pinfunction "S26_34") (pintype "bidirectional"))
    )
    (net (code "22") (name "Net-(U$12-ADDR2)") (class "Default")
      (node (ref "U$12") (pin "1") (pinfunction "SDA_1") (pintype "bidirectional"))
      (node (ref "U$12") (pin "15") (pinfunction "SDA2_15") (pintype "bidirectional"))
      (node (ref "U$12") (pin "19") (pinfunction "ADDR2_19") (pintype "bidirectional"))
      (node (ref "U$12") (pin "22") (pinfunction "SDA3_22") (pintype "bidirectional"))
      (node (ref "U$12") (pin "33") (pinfunction "R2+_33") (pintype "passive"))
      (node (ref "U$12") (pin "8") (pinfunction "SDA1_8") (pintype "bidirectional"))
      (node (ref "U$26") (pin "4") (pinfunction "S9_4") (pintype "bidirectional"))
    )
    (net (code "23") (name "Net-(U$12-ADDR3)") (class "Default")
      (node (ref "U$12") (pin "10") (pinfunction "SCL1_10") (pintype "bidirectional"))
      (node (ref "U$12") (pin "17") (pinfunction "SCL2_17") (pintype "bidirectional"))
      (node (ref "U$12") (pin "24") (pinfunction "SCL3_24") (pintype "bidirectional"))
      (node (ref "U$12") (pin "26") (pinfunction "ADDR3_26") (pintype "bidirectional"))
      (node (ref "U$12") (pin "3") (pinfunction "SCL_3") (pintype "bidirectional"))
      (node (ref "U$12") (pin "31") (pinfunction "R1+_31") (pintype "passive"))
      (node (ref "U$27") (pin "33") (pinfunction "S25_33") (pintype "bidirectional"))
    )
    (net (code "24") (name "Net-(U$13-ADDR2)") (class "Default")
      (node (ref "U$13") (pin "1") (pinfunction "SDA_1") (pintype "bidirectional"))
      (node (ref "U$13") (pin "15") (pinfunction "SDA2_15") (pintype "bidirectional"))
      (node (ref "U$13") (pin "19") (pinfunction "ADDR2_19") (pintype "bidirectional"))
      (node (ref "U$13") (pin "22") (pinfunction "SDA3_22") (pintype "bidirectional"))
      (node (ref "U$13") (pin "33") (pinfunction "R2+_33") (pintype "passive"))
      (node (ref "U$13") (pin "8") (pinfunction "SDA1_8") (pintype "bidirectional"))
      (node (ref "U$26") (pin "33") (pinfunction "S25_33") (pintype "bidirectional"))
    )
    (net (code "25") (name "Net-(U$13-ADDR3)") (class "Default")
      (node (ref "U$13") (pin "10") (pinfunction "SCL1_10") (pintype "bidirectional"))
      (node (ref "U$13") (pin "17") (pinfunction "SCL2_17") (pintype "bidirectional"))
      (node (ref "U$13") (pin "24") (pinfunction "SCL3_24") (pintype "bidirectional"))
      (node (ref "U$13") (pin "26") (pinfunction "ADDR3_26") (pintype "bidirectional"))
      (node (ref "U$13") (pin "3") (pinfunction "SCL_3") (pintype "bidirectional"))
      (node (ref "U$13") (pin "31") (pinfunction "R1+_31") (pintype "passive"))
      (node (ref "U$27") (pin "4") (pinfunction "S9_4") (pintype "bidirectional"))
    )
    (net (code "26") (name "Net-(U$14-ADDR2)") (class "Default")
      (node (ref "U$14") (pin "1") (pinfunction "SDA_1") (pintype "bidirectional"))
      (node (ref "U$14") (pin "15") (pinfunction "SDA2_15") (pintype "bidirectional"))
      (node (ref "U$14") (pin "19") (pinfunction "ADDR2_19") (pintype "bidirectional"))
      (node (ref "U$14") (pin "22") (pinfunction "SDA3_22") (pintype "bidirectional"))
      (node (ref "U$14") (pin "33") (pinfunction "R2+_33") (pintype "passive"))
      (node (ref "U$14") (pin "8") (pinfunction "SDA1_8") (pintype "bidirectional"))
      (node (ref "U$26") (pin "34") (pinfunction "S26_34") (pintype "bidirectional"))
    )
    (net (code "27") (name "Net-(U$14-ADDR3)") (class "Default")
      (node (ref "U$14") (pin "10") (pinfunction "SCL1_10") (pintype "bidirectional"))
      (node (ref "U$14") (pin "17") (pinfunction "SCL2_17") (pintype "bidirectional"))
      (node (ref "U$14") (pin "24") (pinfunction "SCL3_24") (pintype "bidirectional"))
      (node (ref "U$14") (pin "26") (pinfunction "ADDR3_26") (pintype "bidirectional"))
      (node (ref "U$14") (pin "3") (pinfunction "SCL_3") (pintype "bidirectional"))
      (node (ref "U$14") (pin "31") (pinfunction "R1+_31") (pintype "passive"))
      (node (ref "U$27") (pin "3") (pinfunction "S10_3") (pintype "bidirectional"))
    )
    (net (code "28") (name "Net-(U$15-ADDR2)") (class "Default")
      (node (ref "U$15") (pin "1") (pinfunction "SDA_1") (pintype "bidirectional"))
      (node (ref "U$15") (pin "15") (pinfunction "SDA2_15") (pintype "bidirectional"))
      (node (ref "U$15") (pin "19") (pinfunction "ADDR2_19") (pintype "bidirectional"))
      (node (ref "U$15") (pin "22") (pinfunction "SDA3_22") (pintype "bidirectional"))
      (node (ref "U$15") (pin "33") (pinfunction "R2+_33") (pintype "passive"))
      (node (ref "U$15") (pin "8") (pinfunction "SDA1_8") (pintype "bidirectional"))
      (node (ref "U$26") (pin "35") (pinfunction "S27_35") (pintype "bidirectional"))
    )
    (net (code "29") (name "Net-(U$15-ADDR3)") (class "Default")
      (node (ref "U$15") (pin "10") (pinfunction "SCL1_10") (pintype "bidirectional"))
      (node (ref "U$15") (pin "17") (pinfunction "SCL2_17") (pintype "bidirectional"))
      (node (ref "U$15") (pin "24") (pinfunction "SCL3_24") (pintype "bidirectional"))
      (node (ref "U$15") (pin "26") (pinfunction "ADDR3_26") (pintype "bidirectional"))
      (node (ref "U$15") (pin "3") (pinfunction "SCL_3") (pintype "bidirectional"))
      (node (ref "U$15") (pin "31") (pinfunction "R1+_31") (pintype "passive"))
      (node (ref "U$27") (pin "2") (pinfunction "S11_2") (pintype "bidirectional"))
    )
    (net (code "30") (name "Net-(U$16-ADDR2)") (class "Default")
      (node (ref "U$16") (pin "1") (pinfunction "SDA_1") (pintype "bidirectional"))
      (node (ref "U$16") (pin "15") (pinfunction "SDA2_15") (pintype "bidirectional"))
      (node (ref "U$16") (pin "19") (pinfunction "ADDR2_19") (pintype "bidirectional"))
      (node (ref "U$16") (pin "22") (pinfunction "SDA3_22") (pintype "bidirectional"))
      (node (ref "U$16") (pin "33") (pinfunction "R2+_33") (pintype "passive"))
      (node (ref "U$16") (pin "8") (pinfunction "SDA1_8") (pintype "bidirectional"))
      (node (ref "U$26") (pin "36") (pinfunction "S28_36") (pintype "bidirectional"))
    )
    (net (code "31") (name "Net-(U$16-ADDR3)") (class "Default")
      (node (ref "U$16") (pin "10") (pinfunction "SCL1_10") (pintype "bidirectional"))
      (node (ref "U$16") (pin "17") (pinfunction "SCL2_17") (pintype "bidirectional"))
      (node (ref "U$16") (pin "24") (pinfunction "SCL3_24") (pintype "bidirectional"))
      (node (ref "U$16") (pin "26") (pinfunction "ADDR3_26") (pintype "bidirectional"))
      (node (ref "U$16") (pin "3") (pinfunction "SCL_3") (pintype "bidirectional"))
      (node (ref "U$16") (pin "31") (pinfunction "R1+_31") (pintype "passive"))
      (node (ref "U$27") (pin "1") (pinfunction "S12_1") (pintype "bidirectional"))
    )
    (net (code "32") (name "Net-(U$17-ADDR2)") (class "Default")
      (node (ref "U$17") (pin "1") (pinfunction "SDA_1") (pintype "bidirectional"))
      (node (ref "U$17") (pin "15") (pinfunction "SDA2_15") (pintype "bidirectional"))
      (node (ref "U$17") (pin "19") (pinfunction "ADDR2_19") (pintype "bidirectional"))
      (node (ref "U$17") (pin "22") (pinfunction "SDA3_22") (pintype "bidirectional"))
      (node (ref "U$17") (pin "33") (pinfunction "R2+_33") (pintype "passive"))
      (node (ref "U$17") (pin "8") (pinfunction "SDA1_8") (pintype "bidirectional"))
      (node (ref "U$26") (pin "29") (pinfunction "S21_29") (pintype "bidirectional"))
    )
    (net (code "33") (name "Net-(U$17-ADDR3)") (class "Default")
      (node (ref "U$17") (pin "10") (pinfunction "SCL1_10") (pintype "bidirectional"))
      (node (ref "U$17") (pin "17") (pinfunction "SCL2_17") (pintype "bidirectional"))
      (node (ref "U$17") (pin "24") (pinfunction "SCL3_24") (pintype "bidirectional"))
      (node (ref "U$17") (pin "26") (pinfunction "ADDR3_26") (pintype "bidirectional"))
      (node (ref "U$17") (pin "3") (pinfunction "SCL_3") (pintype "bidirectional"))
      (node (ref "U$17") (pin "31") (pinfunction "R1+_31") (pintype "passive"))
      (node (ref "U$27") (pin "8") (pinfunction "S5_8") (pintype "bidirectional"))
    )
    (net (code "34") (name "Net-(U$18-ADDR2)") (class "Default")
      (node (ref "U$18") (pin "1") (pinfunction "SDA_1") (pintype "bidirectional"))
      (node (ref "U$18") (pin "15") (pinfunction "SDA2_15") (pintype "bidirectional"))
      (node (ref "U$18") (pin "19") (pinfunction "ADDR2_19") (pintype "bidirectional"))
      (node (ref "U$18") (pin "22") (pinfunction "SDA3_22") (pintype "bidirectional"))
      (node (ref "U$18") (pin "33") (pinfunction "R2+_33") (pintype "passive"))
      (node (ref "U$18") (pin "8") (pinfunction "SDA1_8") (pintype "bidirectional"))
      (node (ref "U$26") (pin "30") (pinfunction "S22_30") (pintype "bidirectional"))
    )
    (net (code "35") (name "Net-(U$18-ADDR3)") (class "Default")
      (node (ref "U$18") (pin "10") (pinfunction "SCL1_10") (pintype "bidirectional"))
      (node (ref "U$18") (pin "17") (pinfunction "SCL2_17") (pintype "bidirectional"))
      (node (ref "U$18") (pin "24") (pinfunction "SCL3_24") (pintype "bidirectional"))
      (node (ref "U$18") (pin "26") (pinfunction "ADDR3_26") (pintype "bidirectional"))
      (node (ref "U$18") (pin "3") (pinfunction "SCL_3") (pintype "bidirectional"))
      (node (ref "U$18") (pin "31") (pinfunction "R1+_31") (pintype "passive"))
      (node (ref "U$27") (pin "7") (pinfunction "S6_7") (pintype "bidirectional"))
    )
    (net (code "36") (name "Net-(U$19-ADDR2)") (class "Default")
      (node (ref "U$19") (pin "1") (pinfunction "SDA_1") (pintype "bidirectional"))
      (node (ref "U$19") (pin "15") (pinfunction "SDA2_15") (pintype "bidirectional"))
      (node (ref "U$19") (pin "19") (pinfunction "ADDR2_19") (pintype "bidirectional"))
      (node (ref "U$19") (pin "22") (pinfunction "SDA3_22") (pintype "bidirectional"))
      (node (ref "U$19") (pin "33") (pinfunction "R2+_33") (pintype "passive"))
      (node (ref "U$19") (pin "8") (pinfunction "SDA1_8") (pintype "bidirectional"))
      (node (ref "U$26") (pin "31") (pinfunction "S23_31") (pintype "bidirectional"))
    )
    (net (code "37") (name "Net-(U$19-ADDR3)") (class "Default")
      (node (ref "U$19") (pin "10") (pinfunction "SCL1_10") (pintype "bidirectional"))
      (node (ref "U$19") (pin "17") (pinfunction "SCL2_17") (pintype "bidirectional"))
      (node (ref "U$19") (pin "24") (pinfunction "SCL3_24") (pintype "bidirectional"))
      (node (ref "U$19") (pin "26") (pinfunction "ADDR3_26") (pintype "bidirectional"))
      (node (ref "U$19") (pin "3") (pinfunction "SCL_3") (pintype "bidirectional"))
      (node (ref "U$19") (pin "31") (pinfunction "R1+_31") (pintype "passive"))
      (node (ref "U$27") (pin "6") (pinfunction "S7_6") (pintype "bidirectional"))
    )
    (net (code "38") (name "Net-(U$20-ADDR2)") (class "Default")
      (node (ref "U$20") (pin "1") (pinfunction "SDA_1") (pintype "bidirectional"))
      (node (ref "U$20") (pin "15") (pinfunction "SDA2_15") (pintype "bidirectional"))
      (node (ref "U$20") (pin "19") (pinfunction "ADDR2_19") (pintype "bidirectional"))
      (node (ref "U$20") (pin "22") (pinfunction "SDA3_22") (pintype "bidirectional"))
      (node (ref "U$20") (pin "33") (pinfunction "R2+_33") (pintype "passive"))
      (node (ref "U$20") (pin "8") (pinfunction "SDA1_8") (pintype "bidirectional"))
      (node (ref "U$26") (pin "32") (pinfunction "S24_32") (pintype "bidirectional"))
    )
    (net (code "39") (name "Net-(U$20-ADDR3)") (class "Default")
      (node (ref "U$20") (pin "10") (pinfunction "SCL1_10") (pintype "bidirectional"))
      (node (ref "U$20") (pin "17") (pinfunction "SCL2_17") (pintype "bidirectional"))
      (node (ref "U$20") (pin "24") (pinfunction "SCL3_24") (pintype "bidirectional"))
      (node (ref "U$20") (pin "26") (pinfunction "ADDR3_26") (pintype "bidirectional"))
      (node (ref "U$20") (pin "3") (pinfunction "SCL_3") (pintype "bidirectional"))
      (node (ref "U$20") (pin "31") (pinfunction "R1+_31") (pintype "passive"))
      (node (ref "U$27") (pin "5") (pinfunction "S8_5") (pintype "bidirectional"))
    )
    (net (code "40") (name "Net-(U$21-ADDR2)") (class "Default")
      (node (ref "U$21") (pin "1") (pinfunction "SDA_1") (pintype "bidirectional"))
      (node (ref "U$21") (pin "15") (pinfunction "SDA2_15") (pintype "bidirectional"))
      (node (ref "U$21") (pin "19") (pinfunction "ADDR2_19") (pintype "bidirectional"))
      (node (ref "U$21") (pin "22") (pinfunction "SDA3_22") (pintype "bidirectional"))
      (node (ref "U$21") (pin "33") (pinfunction "R2+_33") (pintype "passive"))
      (node (ref "U$21") (pin "8") (pinfunction "SDA1_8") (pintype "bidirectional"))
      (node (ref "U$26") (pin "25") (pinfunction "S17_25") (pintype "bidirectional"))
    )
    (net (code "41") (name "Net-(U$21-ADDR3)") (class "Default")
      (node (ref "U$21") (pin "10") (pinfunction "SCL1_10") (pintype "bidirectional"))
      (node (ref "U$21") (pin "17") (pinfunction "SCL2_17") (pintype "bidirectional"))
      (node (ref "U$21") (pin "24") (pinfunction "SCL3_24") (pintype "bidirectional"))
      (node (ref "U$21") (pin "26") (pinfunction "ADDR3_26") (pintype "bidirectional"))
      (node (ref "U$21") (pin "3") (pinfunction "SCL_3") (pintype "bidirectional"))
      (node (ref "U$21") (pin "31") (pinfunction "R1+_31") (pintype "passive"))
      (node (ref "U$27") (pin "12") (pinfunction "S1_12") (pintype "bidirectional"))
    )
    (net (code "42") (name "Net-(U$22-ADDR2)") (class "Default")
      (node (ref "U$22") (pin "1") (pinfunction "SDA_1") (pintype "bidirectional"))
      (node (ref "U$22") (pin "15") (pinfunction "SDA2_15") (pintype "bidirectional"))
      (node (ref "U$22") (pin "19") (pinfunction "ADDR2_19") (pintype "bidirectional"))
      (node (ref "U$22") (pin "22") (pinfunction "SDA3_22") (pintype "bidirectional"))
      (node (ref "U$22") (pin "33") (pinfunction "R2+_33") (pintype "passive"))
      (node (ref "U$22") (pin "8") (pinfunction "SDA1_8") (pintype "bidirectional"))
      (node (ref "U$26") (pin "26") (pinfunction "S18_26") (pintype "bidirectional"))
    )
    (net (code "43") (name "Net-(U$22-ADDR3)") (class "Default")
      (node (ref "U$22") (pin "10") (pinfunction "SCL1_10") (pintype "bidirectional"))
      (node (ref "U$22") (pin "17") (pinfunction "SCL2_17") (pintype "bidirectional"))
      (node (ref "U$22") (pin "24") (pinfunction "SCL3_24") (pintype "bidirectional"))
      (node (ref "U$22") (pin "26") (pinfunction "ADDR3_26") (pintype "bidirectional"))
      (node (ref "U$22") (pin "3") (pinfunction "SCL_3") (pintype "bidirectional"))
      (node (ref "U$22") (pin "31") (pinfunction "R1+_31") (pintype "passive"))
      (node (ref "U$27") (pin "11") (pinfunction "S2_11") (pintype "bidirectional"))
    )
    (net (code "44") (name "Net-(U$23-ADDR2)") (class "Default")
      (node (ref "U$23") (pin "1") (pinfunction "SDA_1") (pintype "bidirectional"))
      (node (ref "U$23") (pin "15") (pinfunction "SDA2_15") (pintype "bidirectional"))
      (node (ref "U$23") (pin "19") (pinfunction "ADDR2_19") (pintype "bidirectional"))
      (node (ref "U$23") (pin "22") (pinfunction "SDA3_22") (pintype "bidirectional"))
      (node (ref "U$23") (pin "33") (pinfunction "R2+_33") (pintype "passive"))
      (node (ref "U$23") (pin "8") (pinfunction "SDA1_8") (pintype "bidirectional"))
      (node (ref "U$26") (pin "27") (pinfunction "S19_27") (pintype "bidirectional"))
    )
    (net (code "45") (name "Net-(U$23-ADDR3)") (class "Default")
      (node (ref "U$23") (pin "10") (pinfunction "SCL1_10") (pintype "bidirectional"))
      (node (ref "U$23") (pin "17") (pinfunction "SCL2_17") (pintype "bidirectional"))
      (node (ref "U$23") (pin "24") (pinfunction "SCL3_24") (pintype "bidirectional"))
      (node (ref "U$23") (pin "26") (pinfunction "ADDR3_26") (pintype "bidirectional"))
      (node (ref "U$23") (pin "3") (pinfunction "SCL_3") (pintype "bidirectional"))
      (node (ref "U$23") (pin "31") (pinfunction "R1+_31") (pintype "passive"))
      (node (ref "U$27") (pin "10") (pinfunction "S3_10") (pintype "bidirectional"))
    )
    (net (code "46") (name "Net-(U$24-ADDR2)") (class "Default")
      (node (ref "U$24") (pin "1") (pinfunction "SDA_1") (pintype "bidirectional"))
      (node (ref "U$24") (pin "15") (pinfunction "SDA2_15") (pintype "bidirectional"))
      (node (ref "U$24") (pin "19") (pinfunction "ADDR2_19") (pintype "bidirectional"))
      (node (ref "U$24") (pin "22") (pinfunction "SDA3_22") (pintype "bidirectional"))
      (node (ref "U$24") (pin "33") (pinfunction "R2+_33") (pintype "passive"))
      (node (ref "U$24") (pin "8") (pinfunction "SDA1_8") (pintype "bidirectional"))
      (node (ref "U$26") (pin "28") (pinfunction "S20_28") (pintype "bidirectional"))
    )
    (net (code "47") (name "Net-(U$24-ADDR3)") (class "Default")
      (node (ref "U$24") (pin "10") (pinfunction "SCL1_10") (pintype "bidirectional"))
      (node (ref "U$24") (pin "17") (pinfunction "SCL2_17") (pintype "bidirectional"))
      (node (ref "U$24") (pin "24") (pinfunction "SCL3_24") (pintype "bidirectional"))
      (node (ref "U$24") (pin "26") (pinfunction "ADDR3_26") (pintype "bidirectional"))
      (node (ref "U$24") (pin "3") (pinfunction "SCL_3") (pintype "bidirectional"))
      (node (ref "U$24") (pin "31") (pinfunction "R1+_31") (pintype "passive"))
      (node (ref "U$27") (pin "9") (pinfunction "S4_9") (pintype "bidirectional"))
    )
    (net (code "48") (name "Net-(U$26-D)") (class "Default")
      (node (ref "JP1") (pin "12") (pinfunction "12_12") (pintype "passive"))
      (node (ref "R2") (pin "1") (pinfunction "1_1") (pintype "passive"))
      (node (ref "U$26") (pin "43") (pinfunction "D_43") (pintype "bidirectional"))
    )
    (net (code "49") (name "Net-(U$26-S1)") (class "Default")
      (node (ref "U$26") (pin "12") (pinfunction "S1_12") (pintype "bidirectional"))
      (node (ref "U$4") (pin "1") (pinfunction "SDA_1") (pintype "bidirectional"))
      (node (ref "U$4") (pin "15") (pinfunction "SDA2_15") (pintype "bidirectional"))
      (node (ref "U$4") (pin "19") (pinfunction "ADDR2_19") (pintype "bidirectional"))
      (node (ref "U$4") (pin "22") (pinfunction "SDA3_22") (pintype "bidirectional"))
      (node (ref "U$4") (pin "33") (pinfunction "R2+_33") (pintype "passive"))
      (node (ref "U$4") (pin "8") (pinfunction "SDA1_8") (pintype "bidirectional"))
    )
    (net (code "50") (name "Net-(U$26-S2)") (class "Default")
      (node (ref "U$26") (pin "11") (pinfunction "S2_11") (pintype "bidirectional"))
      (node (ref "U$3") (pin "1") (pinfunction "SDA_1") (pintype "bidirectional"))
      (node (ref "U$3") (pin "15") (pinfunction "SDA2_15") (pintype "bidirectional"))
      (node (ref "U$3") (pin "19") (pinfunction "ADDR2_19") (pintype "bidirectional"))
      (node (ref "U$3") (pin "22") (pinfunction "SDA3_22") (pintype "bidirectional"))
      (node (ref "U$3") (pin "33") (pinfunction "R2+_33") (pintype "passive"))
      (node (ref "U$3") (pin "8") (pinfunction "SDA1_8") (pintype "bidirectional"))
    )
    (net (code "51") (name "Net-(U$26-S5)") (class "Default")
      (node (ref "U$26") (pin "8") (pinfunction "S5_8") (pintype "bidirectional"))
      (node (ref "U$8") (pin "1") (pinfunction "SDA_1") (pintype "bidirectional"))
      (node (ref "U$8") (pin "15") (pinfunction "SDA2_15") (pintype "bidirectional"))
      (node (ref "U$8") (pin "19") (pinfunction "ADDR2_19") (pintype "bidirectional"))
      (node (ref "U$8") (pin "22") (pinfunction "SDA3_22") (pintype "bidirectional"))
      (node (ref "U$8") (pin "33") (pinfunction "R2+_33") (pintype "passive"))
      (node (ref "U$8") (pin "8") (pinfunction "SDA1_8") (pintype "bidirectional"))
    )
    (net (code "52") (name "Net-(U$26-S6)") (class "Default")
      (node (ref "U$26") (pin "7") (pinfunction "S6_7") (pintype "bidirectional"))
      (node (ref "U$7") (pin "1") (pinfunction "SDA_1") (pintype "bidirectional"))
      (node (ref "U$7") (pin "15") (pinfunction "SDA2_15") (pintype "bidirectional"))
      (node (ref "U$7") (pin "19") (pinfunction "ADDR2_19") (pintype "bidirectional"))
      (node (ref "U$7") (pin "22") (pinfunction "SDA3_22") (pintype "bidirectional"))
      (node (ref "U$7") (pin "33") (pinfunction "R2+_33") (pintype "passive"))
      (node (ref "U$7") (pin "8") (pinfunction "SDA1_8") (pintype "bidirectional"))
    )
    (net (code "53") (name "Net-(U$26-S7)") (class "Default")
      (node (ref "U$26") (pin "6") (pinfunction "S7_6") (pintype "bidirectional"))
      (node (ref "U$6") (pin "1") (pinfunction "SDA_1") (pintype "bidirectional"))
      (node (ref "U$6") (pin "15") (pinfunction "SDA2_15") (pintype "bidirectional"))
      (node (ref "U$6") (pin "19") (pinfunction "ADDR2_19") (pintype "bidirectional"))
      (node (ref "U$6") (pin "22") (pinfunction "SDA3_22") (pintype "bidirectional"))
      (node (ref "U$6") (pin "33") (pinfunction "R2+_33") (pintype "passive"))
      (node (ref "U$6") (pin "8") (pinfunction "SDA1_8") (pintype "bidirectional"))
    )
    (net (code "54") (name "Net-(U$26-S8)") (class "Default")
      (node (ref "U$26") (pin "5") (pinfunction "S8_5") (pintype "bidirectional"))
      (node (ref "U$5") (pin "1") (pinfunction "SDA_1") (pintype "bidirectional"))
      (node (ref "U$5") (pin "15") (pinfunction "SDA2_15") (pintype "bidirectional"))
      (node (ref "U$5") (pin "19") (pinfunction "ADDR2_19") (pintype "bidirectional"))
      (node (ref "U$5") (pin "22") (pinfunction "SDA3_22") (pintype "bidirectional"))
      (node (ref "U$5") (pin "33") (pinfunction "R2+_33") (pintype "passive"))
      (node (ref "U$5") (pin "8") (pinfunction "SDA1_8") (pintype "bidirectional"))
    )
    (net (code "55") (name "Net-(U$26-S12)") (class "Default")
      (node (ref "U$26") (pin "1") (pinfunction "S12_1") (pintype "bidirectional"))
      (node (ref "U$9") (pin "1") (pinfunction "SDA_1") (pintype "bidirectional"))
      (node (ref "U$9") (pin "15") (pinfunction "SDA2_15") (pintype "bidirectional"))
      (node (ref "U$9") (pin "19") (pinfunction "ADDR2_19") (pintype "bidirectional"))
      (node (ref "U$9") (pin "22") (pinfunction "SDA3_22") (pintype "bidirectional"))
      (node (ref "U$9") (pin "33") (pinfunction "R2+_33") (pintype "passive"))
      (node (ref "U$9") (pin "8") (pinfunction "SDA1_8") (pintype "bidirectional"))
    )
    (net (code "56") (name "Net-(U$27-D)") (class "Default")
      (node (ref "JP1") (pin "11") (pinfunction "11_11") (pintype "passive"))
      (node (ref "R1") (pin "1") (pinfunction "1_1") (pintype "passive"))
      (node (ref "U$27") (pin "43") (pinfunction "D_43") (pintype "bidirectional"))
    )
    (net (code "57") (name "Net-(U$27-S17)") (class "Default")
      (node (ref "U$27") (pin "25") (pinfunction "S17_25") (pintype "bidirectional"))
      (node (ref "U$4") (pin "10") (pinfunction "SCL1_10") (pintype "bidirectional"))
      (node (ref "U$4") (pin "17") (pinfunction "SCL2_17") (pintype "bidirectional"))
      (node (ref "U$4") (pin "24") (pinfunction "SCL3_24") (pintype "bidirectional"))
      (node (ref "U$4") (pin "26") (pinfunction "ADDR3_26") (pintype "bidirectional"))
      (node (ref "U$4") (pin "3") (pinfunction "SCL_3") (pintype "bidirectional"))
      (node (ref "U$4") (pin "31") (pinfunction "R1+_31") (pintype "passive"))
    )
    (net (code "58") (name "Net-(U$27-S18)") (class "Default")
      (node (ref "U$27") (pin "26") (pinfunction "S18_26") (pintype "bidirectional"))
      (node (ref "U$3") (pin "10") (pinfunction "SCL1_10") (pintype "bidirectional"))
      (node (ref "U$3") (pin "17") (pinfunction "SCL2_17") (pintype "bidirectional"))
      (node (ref "U$3") (pin "24") (pinfunction "SCL3_24") (pintype "bidirectional"))
      (node (ref "U$3") (pin "26") (pinfunction "ADDR3_26") (pintype "bidirectional"))
      (node (ref "U$3") (pin "3") (pinfunction "SCL_3") (pintype "bidirectional"))
      (node (ref "U$3") (pin "31") (pinfunction "R1+_31") (pintype "passive"))
    )
    (net (code "59") (name "Net-(U$27-S21)") (class "Default")
      (node (ref "U$27") (pin "29") (pinfunction "S21_29") (pintype "bidirectional"))
      (node (ref "U$8") (pin "10") (pinfunction "SCL1_10") (pintype "bidirectional"))
      (node (ref "U$8") (pin "17") (pinfunction "SCL2_17") (pintype "bidirectional"))
      (node (ref "U$8") (pin "24") (pinfunction "SCL3_24") (pintype "bidirectional"))
      (node (ref "U$8") (pin "26") (pinfunction "ADDR3_26") (pintype "bidirectional"))
      (node (ref "U$8") (pin "3") (pinfunction "SCL_3") (pintype "bidirectional"))
      (node (ref "U$8") (pin "31") (pinfunction "R1+_31") (pintype "passive"))
    )
    (net (code "60") (name "Net-(U$27-S22)") (class "Default")
      (node (ref "U$27") (pin "30") (pinfunction "S22_30") (pintype "bidirectional"))
      (node (ref "U$7") (pin "10") (pinfunction "SCL1_10") (pintype "bidirectional"))
      (node (ref "U$7") (pin "17") (pinfunction "SCL2_17") (pintype "bidirectional"))
      (node (ref "U$7") (pin "24") (pinfunction "SCL3_24") (pintype "bidirectional"))
      (node (ref "U$7") (pin "26") (pinfunction "ADDR3_26") (pintype "bidirectional"))
      (node (ref "U$7") (pin "3") (pinfunction "SCL_3") (pintype "bidirectional"))
      (node (ref "U$7") (pin "31") (pinfunction "R1+_31") (pintype "passive"))
    )
    (net (code "61") (name "Net-(U$27-S23)") (class "Default")
      (node (ref "U$27") (pin "31") (pinfunction "S23_31") (pintype "bidirectional"))
      (node (ref "U$6") (pin "10") (pinfunction "SCL1_10") (pintype "bidirectional"))
      (node (ref "U$6") (pin "17") (pinfunction "SCL2_17") (pintype "bidirectional"))
      (node (ref "U$6") (pin "24") (pinfunction "SCL3_24") (pintype "bidirectional"))
      (node (ref "U$6") (pin "26") (pinfunction "ADDR3_26") (pintype "bidirectional"))
      (node (ref "U$6") (pin "3") (pinfunction "SCL_3") (pintype "bidirectional"))
      (node (ref "U$6") (pin "31") (pinfunction "R1+_31") (pintype "passive"))
    )
    (net (code "62") (name "Net-(U$27-S24)") (class "Default")
      (node (ref "U$27") (pin "32") (pinfunction "S24_32") (pintype "bidirectional"))
      (node (ref "U$5") (pin "10") (pinfunction "SCL1_10") (pintype "bidirectional"))
      (node (ref "U$5") (pin "17") (pinfunction "SCL2_17") (pintype "bidirectional"))
      (node (ref "U$5") (pin "24") (pinfunction "SCL3_24") (pintype "bidirectional"))
      (node (ref "U$5") (pin "26") (pinfunction "ADDR3_26") (pintype "bidirectional"))
      (node (ref "U$5") (pin "3") (pinfunction "SCL_3") (pintype "bidirectional"))
      (node (ref "U$5") (pin "31") (pinfunction "R1+_31") (pintype "passive"))
    )
    (net (code "63") (name "Net-(U$27-S28)") (class "Default")
      (node (ref "U$27") (pin "36") (pinfunction "S28_36") (pintype "bidirectional"))
      (node (ref "U$9") (pin "10") (pinfunction "SCL1_10") (pintype "bidirectional"))
      (node (ref "U$9") (pin "17") (pinfunction "SCL2_17") (pintype "bidirectional"))
      (node (ref "U$9") (pin "24") (pinfunction "SCL3_24") (pintype "bidirectional"))
      (node (ref "U$9") (pin "26") (pinfunction "ADDR3_26") (pintype "bidirectional"))
      (node (ref "U$9") (pin "3") (pinfunction "SCL_3") (pintype "bidirectional"))
      (node (ref "U$9") (pin "31") (pinfunction "R1+_31") (pintype "passive"))
    )
    (net (code "64") (name "VDD") (class "Default")
      (node (ref "JP2") (pin "2") (pinfunction "2_2") (pintype "passive"))
      (node (ref "R1") (pin "2") (pinfunction "2_2") (pintype "passive"))
      (node (ref "R2") (pin "2") (pinfunction "2_2") (pintype "passive"))
      (node (ref "U$1") (pin "12") (pinfunction "ADDR1_12") (pintype "bidirectional"))
      (node (ref "U$1") (pin "13") (pinfunction "VDD1_13") (pintype "bidirectional"))
      (node (ref "U$1") (pin "20") (pinfunction "VDD2_20") (pintype "bidirectional"))
      (node (ref "U$1") (pin "27") (pinfunction "VDD3_27") (pintype "bidirectional"))
      (node (ref "U$1") (pin "29") (pinfunction "C+_29") (pintype "passive"))
      (node (ref "U$1") (pin "32") (pinfunction "GND_32") (pintype "passive"))
      (node (ref "U$1") (pin "34") (pinfunction "GND_34") (pintype "passive"))
      (node (ref "U$1") (pin "6") (pinfunction "VDD_6") (pintype "bidirectional"))
      (node (ref "U$10") (pin "12") (pinfunction "ADDR1_12") (pintype "bidirectional"))
      (node (ref "U$10") (pin "13") (pinfunction "VDD1_13") (pintype "bidirectional"))
      (node (ref "U$10") (pin "20") (pinfunction "VDD2_20") (pintype "bidirectional"))
      (node (ref "U$10") (pin "27") (pinfunction "VDD3_27") (pintype "bidirectional"))
      (node (ref "U$10") (pin "29") (pinfunction "C+_29") (pintype "passive"))
      (node (ref "U$10") (pin "32") (pinfunction "GND_32") (pintype "passive"))
      (node (ref "U$10") (pin "34") (pinfunction "GND_34") (pintype "passive"))
      (node (ref "U$10") (pin "6") (pinfunction "VDD_6") (pintype "bidirectional"))
      (node (ref "U$11") (pin "12") (pinfunction "ADDR1_12") (pintype "bidirectional"))
      (node (ref "U$11") (pin "13") (pinfunction "VDD1_13") (pintype "bidirectional"))
      (node (ref "U$11") (pin "20") (pinfunction "VDD2_20") (pintype "bidirectional"))
      (node (ref "U$11") (pin "27") (pinfunction "VDD3_27") (pintype "bidirectional"))
      (node (ref "U$11") (pin "29") (pinfunction "C+_29") (pintype "passive"))
      (node (ref "U$11") (pin "32") (pinfunction "GND_32") (pintype "passive"))
      (node (ref "U$11") (pin "34") (pinfunction "GND_34") (pintype "passive"))
      (node (ref "U$11") (pin "6") (pinfunction "VDD_6") (pintype "bidirectional"))
      (node (ref "U$12") (pin "12") (pinfunction "ADDR1_12") (pintype "bidirectional"))
      (node (ref "U$12") (pin "13") (pinfunction "VDD1_13") (pintype "bidirectional"))
      (node (ref "U$12") (pin "20") (pinfunction "VDD2_20") (pintype "bidirectional"))
      (node (ref "U$12") (pin "27") (pinfunction "VDD3_27") (pintype "bidirectional"))
      (node (ref "U$12") (pin "29") (pinfunction "C+_29") (pintype "passive"))
      (node (ref "U$12") (pin "32") (pinfunction "GND_32") (pintype "passive"))
      (node (ref "U$12") (pin "34") (pinfunction "GND_34") (pintype "passive"))
      (node (ref "U$12") (pin "6") (pinfunction "VDD_6") (pintype "bidirectional"))
      (node (ref "U$13") (pin "12") (pinfunction "ADDR1_12") (pintype "bidirectional"))
      (node (ref "U$13") (pin "13") (pinfunction "VDD1_13") (pintype "bidirectional"))
      (node (ref "U$13") (pin "20") (pinfunction "VDD2_20") (pintype "bidirectional"))
      (node (ref "U$13") (pin "27") (pinfunction "VDD3_27") (pintype "bidirectional"))
      (node (ref "U$13") (pin "29") (pinfunction "C+_29") (pintype "passive"))
      (node (ref "U$13") (pin "32") (pinfunction "GND_32") (pintype "passive"))
      (node (ref "U$13") (pin "34") (pinfunction "GND_34") (pintype "passive"))
      (node (ref "U$13") (pin "6") (pinfunction "VDD_6") (pintype "bidirectional"))
      (node (ref "U$14") (pin "12") (pinfunction "ADDR1_12") (pintype "bidirectional"))
      (node (ref "U$14") (pin "13") (pinfunction "VDD1_13") (pintype "bidirectional"))
      (node (ref "U$14") (pin "20") (pinfunction "VDD2_20") (pintype "bidirectional"))
      (node (ref "U$14") (pin "27") (pinfunction "VDD3_27") (pintype "bidirectional"))
      (node (ref "U$14") (pin "29") (pinfunction "C+_29") (pintype "passive"))
      (node (ref "U$14") (pin "32") (pinfunction "GND_32") (pintype "passive"))
      (node (ref "U$14") (pin "34") (pinfunction "GND_34") (pintype "passive"))
      (node (ref "U$14") (pin "6") (pinfunction "VDD_6") (pintype "bidirectional"))
      (node (ref "U$15") (pin "12") (pinfunction "ADDR1_12") (pintype "bidirectional"))
      (node (ref "U$15") (pin "13") (pinfunction "VDD1_13") (pintype "bidirectional"))
      (node (ref "U$15") (pin "20") (pinfunction "VDD2_20") (pintype "bidirectional"))
      (node (ref "U$15") (pin "27") (pinfunction "VDD3_27") (pintype "bidirectional"))
      (node (ref "U$15") (pin "29") (pinfunction "C+_29") (pintype "passive"))
      (node (ref "U$15") (pin "32") (pinfunction "GND_32") (pintype "passive"))
      (node (ref "U$15") (pin "34") (pinfunction "GND_34") (pintype "passive"))
      (node (ref "U$15") (pin "6") (pinfunction "VDD_6") (pintype "bidirectional"))
      (node (ref "U$16") (pin "12") (pinfunction "ADDR1_12") (pintype "bidirectional"))
      (node (ref "U$16") (pin "13") (pinfunction "VDD1_13") (pintype "bidirectional"))
      (node (ref "U$16") (pin "20") (pinfunction "VDD2_20") (pintype "bidirectional"))
      (node (ref "U$16") (pin "27") (pinfunction "VDD3_27") (pintype "bidirectional"))
      (node (ref "U$16") (pin "29") (pinfunction "C+_29") (pintype "passive"))
      (node (ref "U$16") (pin "32") (pinfunction "GND_32") (pintype "passive"))
      (node (ref "U$16") (pin "34") (pinfunction "GND_34") (pintype "passive"))
      (node (ref "U$16") (pin "6") (pinfunction "VDD_6") (pintype "bidirectional"))
      (node (ref "U$17") (pin "12") (pinfunction "ADDR1_12") (pintype "bidirectional"))
      (node (ref "U$17") (pin "13") (pinfunction "VDD1_13") (pintype "bidirectional"))
      (node (ref "U$17") (pin "20") (pinfunction "VDD2_20") (pintype "bidirectional"))
      (node (ref "U$17") (pin "27") (pinfunction "VDD3_27") (pintype "bidirectional"))
      (node (ref "U$17") (pin "29") (pinfunction "C+_29") (pintype "passive"))
      (node (ref "U$17") (pin "32") (pinfunction "GND_32") (pintype "passive"))
      (node (ref "U$17") (pin "34") (pinfunction "GND_34") (pintype "passive"))
      (node (ref "U$17") (pin "6") (pinfunction "VDD_6") (pintype "bidirectional"))
      (node (ref "U$18") (pin "12") (pinfunction "ADDR1_12") (pintype "bidirectional"))
      (node (ref "U$18") (pin "13") (pinfunction "VDD1_13") (pintype "bidirectional"))
      (node (ref "U$18") (pin "20") (pinfunction "VDD2_20") (pintype "bidirectional"))
      (node (ref "U$18") (pin "27") (pinfunction "VDD3_27") (pintype "bidirectional"))
      (node (ref "U$18") (pin "29") (pinfunction "C+_29") (pintype "passive"))
      (node (ref "U$18") (pin "32") (pinfunction "GND_32") (pintype "passive"))
      (node (ref "U$18") (pin "34") (pinfunction "GND_34") (pintype "passive"))
      (node (ref "U$18") (pin "6") (pinfunction "VDD_6") (pintype "bidirectional"))
      (node (ref "U$19") (pin "12") (pinfunction "ADDR1_12") (pintype "bidirectional"))
      (node (ref "U$19") (pin "13") (pinfunction "VDD1_13") (pintype "bidirectional"))
      (node (ref "U$19") (pin "20") (pinfunction "VDD2_20") (pintype "bidirectional"))
      (node (ref "U$19") (pin "27") (pinfunction "VDD3_27") (pintype "bidirectional"))
      (node (ref "U$19") (pin "29") (pinfunction "C+_29") (pintype "passive"))
      (node (ref "U$19") (pin "32") (pinfunction "GND_32") (pintype "passive"))
      (node (ref "U$19") (pin "34") (pinfunction "GND_34") (pintype "passive"))
      (node (ref "U$19") (pin "6") (pinfunction "VDD_6") (pintype "bidirectional"))
      (node (ref "U$2") (pin "12") (pinfunction "ADDR1_12") (pintype "bidirectional"))
      (node (ref "U$2") (pin "13") (pinfunction "VDD1_13") (pintype "bidirectional"))
      (node (ref "U$2") (pin "20") (pinfunction "VDD2_20") (pintype "bidirectional"))
      (node (ref "U$2") (pin "27") (pinfunction "VDD3_27") (pintype "bidirectional"))
      (node (ref "U$2") (pin "29") (pinfunction "C+_29") (pintype "passive"))
      (node (ref "U$2") (pin "32") (pinfunction "GND_32") (pintype "passive"))
      (node (ref "U$2") (pin "34") (pinfunction "GND_34") (pintype "passive"))
      (node (ref "U$2") (pin "6") (pinfunction "VDD_6") (pintype "bidirectional"))
      (node (ref "U$20") (pin "12") (pinfunction "ADDR1_12") (pintype "bidirectional"))
      (node (ref "U$20") (pin "13") (pinfunction "VDD1_13") (pintype "bidirectional"))
      (node (ref "U$20") (pin "20") (pinfunction "VDD2_20") (pintype "bidirectional"))
      (node (ref "U$20") (pin "27") (pinfunction "VDD3_27") (pintype "bidirectional"))
      (node (ref "U$20") (pin "29") (pinfunction "C+_29") (pintype "passive"))
      (node (ref "U$20") (pin "32") (pinfunction "GND_32") (pintype "passive"))
      (node (ref "U$20") (pin "34") (pinfunction "GND_34") (pintype "passive"))
      (node (ref "U$20") (pin "6") (pinfunction "VDD_6") (pintype "bidirectional"))
      (node (ref "U$21") (pin "12") (pinfunction "ADDR1_12") (pintype "bidirectional"))
      (node (ref "U$21") (pin "13") (pinfunction "VDD1_13") (pintype "bidirectional"))
      (node (ref "U$21") (pin "20") (pinfunction "VDD2_20") (pintype "bidirectional"))
      (node (ref "U$21") (pin "27") (pinfunction "VDD3_27") (pintype "bidirectional"))
      (node (ref "U$21") (pin "29") (pinfunction "C+_29") (pintype "passive"))
      (node (ref "U$21") (pin "32") (pinfunction "GND_32") (pintype "passive"))
      (node (ref "U$21") (pin "34") (pinfunction "GND_34") (pintype "passive"))
      (node (ref "U$21") (pin "6") (pinfunction "VDD_6") (pintype "bidirectional"))
      (node (ref "U$22") (pin "12") (pinfunction "ADDR1_12") (pintype "bidirectional"))
      (node (ref "U$22") (pin "13") (pinfunction "VDD1_13") (pintype "bidirectional"))
      (node (ref "U$22") (pin "20") (pinfunction "VDD2_20") (pintype "bidirectional"))
      (node (ref "U$22") (pin "27") (pinfunction "VDD3_27") (pintype "bidirectional"))
      (node (ref "U$22") (pin "29") (pinfunction "C+_29") (pintype "passive"))
      (node (ref "U$22") (pin "32") (pinfunction "GND_32") (pintype "passive"))
      (node (ref "U$22") (pin "34") (pinfunction "GND_34") (pintype "passive"))
      (node (ref "U$22") (pin "6") (pinfunction "VDD_6") (pintype "bidirectional"))
      (node (ref "U$23") (pin "12") (pinfunction "ADDR1_12") (pintype "bidirectional"))
      (node (ref "U$23") (pin "13") (pinfunction "VDD1_13") (pintype "bidirectional"))
      (node (ref "U$23") (pin "20") (pinfunction "VDD2_20") (pintype "bidirectional"))
      (node (ref "U$23") (pin "27") (pinfunction "VDD3_27") (pintype "bidirectional"))
      (node (ref "U$23") (pin "29") (pinfunction "C+_29") (pintype "passive"))
      (node (ref "U$23") (pin "32") (pinfunction "GND_32") (pintype "passive"))
      (node (ref "U$23") (pin "34") (pinfunction "GND_34") (pintype "passive"))
      (node (ref "U$23") (pin "6") (pinfunction "VDD_6") (pintype "bidirectional"))
      (node (ref "U$24") (pin "12") (pinfunction "ADDR1_12") (pintype "bidirectional"))
      (node (ref "U$24") (pin "13") (pinfunction "VDD1_13") (pintype "bidirectional"))
      (node (ref "U$24") (pin "20") (pinfunction "VDD2_20") (pintype "bidirectional"))
      (node (ref "U$24") (pin "27") (pinfunction "VDD3_27") (pintype "bidirectional"))
      (node (ref "U$24") (pin "29") (pinfunction "C+_29") (pintype "passive"))
      (node (ref "U$24") (pin "32") (pinfunction "GND_32") (pintype "passive"))
      (node (ref "U$24") (pin "34") (pinfunction "GND_34") (pintype "passive"))
      (node (ref "U$24") (pin "6") (pinfunction "VDD_6") (pintype "bidirectional"))
      (node (ref "U$25") (pin "5") (pinfunction "P$5_5") (pintype "bidirectional"))
      (node (ref "U$26") (pin "13") (pinfunction "VDD_13") (pintype "bidirectional"))
      (node (ref "U$26") (pin "14") (pinfunction "VDD_14") (pintype "bidirectional"))
      (node (ref "U$27") (pin "13") (pinfunction "VDD_13") (pintype "bidirectional"))
      (node (ref "U$27") (pin "14") (pinfunction "VDD_14") (pintype "bidirectional"))
      (node (ref "U$3") (pin "12") (pinfunction "ADDR1_12") (pintype "bidirectional"))
      (node (ref "U$3") (pin "13") (pinfunction "VDD1_13") (pintype "bidirectional"))
      (node (ref "U$3") (pin "20") (pinfunction "VDD2_20") (pintype "bidirectional"))
      (node (ref "U$3") (pin "27") (pinfunction "VDD3_27") (pintype "bidirectional"))
      (node (ref "U$3") (pin "29") (pinfunction "C+_29") (pintype "passive"))
      (node (ref "U$3") (pin "32") (pinfunction "GND_32") (pintype "passive"))
      (node (ref "U$3") (pin "34") (pinfunction "GND_34") (pintype "passive"))
      (node (ref "U$3") (pin "6") (pinfunction "VDD_6") (pintype "bidirectional"))
      (node (ref "U$4") (pin "12") (pinfunction "ADDR1_12") (pintype "bidirectional"))
      (node (ref "U$4") (pin "13") (pinfunction "VDD1_13") (pintype "bidirectional"))
      (node (ref "U$4") (pin "20") (pinfunction "VDD2_20") (pintype "bidirectional"))
      (node (ref "U$4") (pin "27") (pinfunction "VDD3_27") (pintype "bidirectional"))
      (node (ref "U$4") (pin "29") (pinfunction "C+_29") (pintype "passive"))
      (node (ref "U$4") (pin "32") (pinfunction "GND_32") (pintype "passive"))
      (node (ref "U$4") (pin "34") (pinfunction "GND_34") (pintype "passive"))
      (node (ref "U$4") (pin "6") (pinfunction "VDD_6") (pintype "bidirectional"))
      (node (ref "U$5") (pin "12") (pinfunction "ADDR1_12") (pintype "bidirectional"))
      (node (ref "U$5") (pin "13") (pinfunction "VDD1_13") (pintype "bidirectional"))
      (node (ref "U$5") (pin "20") (pinfunction "VDD2_20") (pintype "bidirectional"))
      (node (ref "U$5") (pin "27") (pinfunction "VDD3_27") (pintype "bidirectional"))
      (node (ref "U$5") (pin "29") (pinfunction "C+_29") (pintype "passive"))
      (node (ref "U$5") (pin "32") (pinfunction "GND_32") (pintype "passive"))
      (node (ref "U$5") (pin "34") (pinfunction "GND_34") (pintype "passive"))
      (node (ref "U$5") (pin "6") (pinfunction "VDD_6") (pintype "bidirectional"))
      (node (ref "U$6") (pin "12") (pinfunction "ADDR1_12") (pintype "bidirectional"))
      (node (ref "U$6") (pin "13") (pinfunction "VDD1_13") (pintype "bidirectional"))
      (node (ref "U$6") (pin "20") (pinfunction "VDD2_20") (pintype "bidirectional"))
      (node (ref "U$6") (pin "27") (pinfunction "VDD3_27") (pintype "bidirectional"))
      (node (ref "U$6") (pin "29") (pinfunction "C+_29") (pintype "passive"))
      (node (ref "U$6") (pin "32") (pinfunction "GND_32") (pintype "passive"))
      (node (ref "U$6") (pin "34") (pinfunction "GND_34") (pintype "passive"))
      (node (ref "U$6") (pin "6") (pinfunction "VDD_6") (pintype "bidirectional"))
      (node (ref "U$7") (pin "12") (pinfunction "ADDR1_12") (pintype "bidirectional"))
      (node (ref "U$7") (pin "13") (pinfunction "VDD1_13") (pintype "bidirectional"))
      (node (ref "U$7") (pin "20") (pinfunction "VDD2_20") (pintype "bidirectional"))
      (node (ref "U$7") (pin "27") (pinfunction "VDD3_27") (pintype "bidirectional"))
      (node (ref "U$7") (pin "29") (pinfunction "C+_29") (pintype "passive"))
      (node (ref "U$7") (pin "32") (pinfunction "GND_32") (pintype "passive"))
      (node (ref "U$7") (pin "34") (pinfunction "GND_34") (pintype "passive"))
      (node (ref "U$7") (pin "6") (pinfunction "VDD_6") (pintype "bidirectional"))
      (node (ref "U$8") (pin "12") (pinfunction "ADDR1_12") (pintype "bidirectional"))
      (node (ref "U$8") (pin "13") (pinfunction "VDD1_13") (pintype "bidirectional"))
      (node (ref "U$8") (pin "20") (pinfunction "VDD2_20") (pintype "bidirectional"))
      (node (ref "U$8") (pin "27") (pinfunction "VDD3_27") (pintype "bidirectional"))
      (node (ref "U$8") (pin "29") (pinfunction "C+_29") (pintype "passive"))
      (node (ref "U$8") (pin "32") (pinfunction "GND_32") (pintype "passive"))
      (node (ref "U$8") (pin "34") (pinfunction "GND_34") (pintype "passive"))
      (node (ref "U$8") (pin "6") (pinfunction "VDD_6") (pintype "bidirectional"))
      (node (ref "U$9") (pin "12") (pinfunction "ADDR1_12") (pintype "bidirectional"))
      (node (ref "U$9") (pin "13") (pinfunction "VDD1_13") (pintype "bidirectional"))
      (node (ref "U$9") (pin "20") (pinfunction "VDD2_20") (pintype "bidirectional"))
      (node (ref "U$9") (pin "27") (pinfunction "VDD3_27") (pintype "bidirectional"))
      (node (ref "U$9") (pin "29") (pinfunction "C+_29") (pintype "passive"))
      (node (ref "U$9") (pin "32") (pinfunction "GND_32") (pintype "passive"))
      (node (ref "U$9") (pin "34") (pinfunction "GND_34") (pintype "passive"))
      (node (ref "U$9") (pin "6") (pinfunction "VDD_6") (pintype "bidirectional"))
    )
    (net (code "65") (name "unconnected-(JP1-Pad1)") (class "Default")
      (node (ref "JP1") (pin "1") (pinfunction "1_1") (pintype "passive"))
    )
    (net (code "66") (name "unconnected-(JP1-Pad2)") (class "Default")
      (node (ref "JP1") (pin "2") (pinfunction "2_2") (pintype "passive"))
    )
    (net (code "67") (name "unconnected-(JP1-Pad3)") (class "Default")
      (node (ref "JP1") (pin "3") (pinfunction "3_3") (pintype "passive"))
    )
    (net (code "68") (name "unconnected-(JP2-Pad1)") (class "Default")
      (node (ref "JP2") (pin "1") (pinfunction "1_1") (pintype "passive"))
    )
    (net (code "69") (name "unconnected-(JP2-Pad3)") (class "Default")
      (node (ref "JP2") (pin "3") (pinfunction "3_3") (pintype "passive"))
    )
    (net (code "70") (name "unconnected-(JP2-Pad8)") (class "Default")
      (node (ref "JP2") (pin "8") (pinfunction "8_8") (pintype "passive"))
    )
    (net (code "71") (name "unconnected-(JP2-Pad9)") (class "Default")
      (node (ref "JP2") (pin "9") (pinfunction "9_9") (pintype "passive"))
    )
    (net (code "72") (name "unconnected-(JP2-Pad10)") (class "Default")
      (node (ref "JP2") (pin "10") (pinfunction "10_10") (pintype "passive"))
    )
    (net (code "73") (name "unconnected-(JP2-Pad11)") (class "Default")
      (node (ref "JP2") (pin "11") (pinfunction "11_11") (pintype "passive"))
    )
    (net (code "74") (name "unconnected-(JP2-Pad12)") (class "Default")
      (node (ref "JP2") (pin "12") (pinfunction "12_12") (pintype "passive"))
    )
    (net (code "75") (name "unconnected-(JP2-Pad13)") (class "Default")
      (node (ref "JP2") (pin "13") (pinfunction "13_13") (pintype "passive"))
    )
    (net (code "76") (name "unconnected-(U$1-INT-Pad2)") (class "Default")
      (node (ref "U$1") (pin "2") (pinfunction "INT_2") (pintype "bidirectional"))
    )
    (net (code "77") (name "unconnected-(U$1-INT1-Pad9)") (class "Default")
      (node (ref "U$1") (pin "9") (pinfunction "INT1_9") (pintype "bidirectional"))
    )
    (net (code "78") (name "unconnected-(U$1-INT2-Pad16)") (class "Default")
      (node (ref "U$1") (pin "16") (pinfunction "INT2_16") (pintype "bidirectional"))
    )
    (net (code "79") (name "unconnected-(U$1-INT3-Pad23)") (class "Default")
      (node (ref "U$1") (pin "23") (pinfunction "INT3_23") (pintype "bidirectional"))
    )
    (net (code "80") (name "unconnected-(U$2-INT-Pad2)") (class "Default")
      (node (ref "U$2") (pin "2") (pinfunction "INT_2") (pintype "bidirectional"))
    )
    (net (code "81") (name "unconnected-(U$2-INT1-Pad9)") (class "Default")
      (node (ref "U$2") (pin "9") (pinfunction "INT1_9") (pintype "bidirectional"))
    )
    (net (code "82") (name "unconnected-(U$2-INT2-Pad16)") (class "Default")
      (node (ref "U$2") (pin "16") (pinfunction "INT2_16") (pintype "bidirectional"))
    )
    (net (code "83") (name "unconnected-(U$2-INT3-Pad23)") (class "Default")
      (node (ref "U$2") (pin "23") (pinfunction "INT3_23") (pintype "bidirectional"))
    )
    (net (code "84") (name "unconnected-(U$3-INT-Pad2)") (class "Default")
      (node (ref "U$3") (pin "2") (pinfunction "INT_2") (pintype "bidirectional"))
    )
    (net (code "85") (name "unconnected-(U$3-INT1-Pad9)") (class "Default")
      (node (ref "U$3") (pin "9") (pinfunction "INT1_9") (pintype "bidirectional"))
    )
    (net (code "86") (name "unconnected-(U$3-INT2-Pad16)") (class "Default")
      (node (ref "U$3") (pin "16") (pinfunction "INT2_16") (pintype "bidirectional"))
    )
    (net (code "87") (name "unconnected-(U$3-INT3-Pad23)") (class "Default")
      (node (ref "U$3") (pin "23") (pinfunction "INT3_23") (pintype "bidirectional"))
    )
    (net (code "88") (name "unconnected-(U$4-INT-Pad2)") (class "Default")
      (node (ref "U$4") (pin "2") (pinfunction "INT_2") (pintype "bidirectional"))
    )
    (net (code "89") (name "unconnected-(U$4-INT1-Pad9)") (class "Default")
      (node (ref "U$4") (pin "9") (pinfunction "INT1_9") (pintype "bidirectional"))
    )
    (net (code "90") (name "unconnected-(U$4-INT2-Pad16)") (class "Default")
      (node (ref "U$4") (pin "16") (pinfunction "INT2_16") (pintype "bidirectional"))
    )
    (net (code "91") (name "unconnected-(U$4-INT3-Pad23)") (class "Default")
      (node (ref "U$4") (pin "23") (pinfunction "INT3_23") (pintype "bidirectional"))
    )
    (net (code "92") (name "unconnected-(U$5-INT-Pad2)") (class "Default")
      (node (ref "U$5") (pin "2") (pinfunction "INT_2") (pintype "bidirectional"))
    )
    (net (code "93") (name "unconnected-(U$5-INT1-Pad9)") (class "Default")
      (node (ref "U$5") (pin "9") (pinfunction "INT1_9") (pintype "bidirectional"))
    )
    (net (code "94") (name "unconnected-(U$5-INT2-Pad16)") (class "Default")
      (node (ref "U$5") (pin "16") (pinfunction "INT2_16") (pintype "bidirectional"))
    )
    (net (code "95") (name "unconnected-(U$5-INT3-Pad23)") (class "Default")
      (node (ref "U$5") (pin "23") (pinfunction "INT3_23") (pintype "bidirectional"))
    )
    (net (code "96") (name "unconnected-(U$6-INT-Pad2)") (class "Default")
      (node (ref "U$6") (pin "2") (pinfunction "INT_2") (pintype "bidirectional"))
    )
    (net (code "97") (name "unconnected-(U$6-INT1-Pad9)") (class "Default")
      (node (ref "U$6") (pin "9") (pinfunction "INT1_9") (pintype "bidirectional"))
    )
    (net (code "98") (name "unconnected-(U$6-INT2-Pad16)") (class "Default")
      (node (ref "U$6") (pin "16") (pinfunction "INT2_16") (pintype "bidirectional"))
    )
    (net (code "99") (name "unconnected-(U$6-INT3-Pad23)") (class "Default")
      (node (ref "U$6") (pin "23") (pinfunction "INT3_23") (pintype "bidirectional"))
    )
    (net (code "100") (name "unconnected-(U$7-INT-Pad2)") (class "Default")
      (node (ref "U$7") (pin "2") (pinfunction "INT_2") (pintype "bidirectional"))
    )
    (net (code "101") (name "unconnected-(U$7-INT1-Pad9)") (class "Default")
      (node (ref "U$7") (pin "9") (pinfunction "INT1_9") (pintype "bidirectional"))
    )
    (net (code "102") (name "unconnected-(U$7-INT2-Pad16)") (class "Default")
      (node (ref "U$7") (pin "16") (pinfunction "INT2_16") (pintype "bidirectional"))
    )
    (net (code "103") (name "unconnected-(U$7-INT3-Pad23)") (class "Default")
      (node (ref "U$7") (pin "23") (pinfunction "INT3_23") (pintype "bidirectional"))
    )
    (net (code "104") (name "unconnected-(U$8-INT-Pad2)") (class "Default")
      (node (ref "U$8") (pin "2") (pinfunction "INT_2") (pintype "bidirectional"))
    )
    (net (code "105") (name "unconnected-(U$8-INT1-Pad9)") (class "Default")
      (node (ref "U$8") (pin "9") (pinfunction "INT1_9") (pintype "bidirectional"))
    )
    (net (code "106") (name "unconnected-(U$8-INT2-Pad16)") (class "Default")
      (node (ref "U$8") (pin "16") (pinfunction "INT2_16") (pintype "bidirectional"))
    )
    (net (code "107") (name "unconnected-(U$8-INT3-Pad23)") (class "Default")
      (node (ref "U$8") (pin "23") (pinfunction "INT3_23") (pintype "bidirectional"))
    )
    (net (code "108") (name "unconnected-(U$9-INT-Pad2)") (class "Default")
      (node (ref "U$9") (pin "2") (pinfunction "INT_2") (pintype "bidirectional"))
    )
    (net (code "109") (name "unconnected-(U$9-INT1-Pad9)") (class "Default")
      (node (ref "U$9") (pin "9") (pinfunction "INT1_9") (pintype "bidirectional"))
    )
    (net (code "110") (name "unconnected-(U$9-INT2-Pad16)") (class "Default")
      (node (ref "U$9") (pin "16") (pinfunction "INT2_16") (pintype "bidirectional"))
    )
    (net (code "111") (name "unconnected-(U$9-INT3-Pad23)") (class "Default")
      (node (ref "U$9") (pin "23") (pinfunction "INT3_23") (pintype "bidirectional"))
    )
    (net (code "112") (name "unconnected-(U$10-INT-Pad2)") (class "Default")
      (node (ref "U$10") (pin "2") (pinfunction "INT_2") (pintype "bidirectional"))
    )
    (net (code "113") (name "unconnected-(U$10-INT1-Pad9)") (class "Default")
      (node (ref "U$10") (pin "9") (pinfunction "INT1_9") (pintype "bidirectional"))
    )
    (net (code "114") (name "unconnected-(U$10-INT2-Pad16)") (class "Default")
      (node (ref "U$10") (pin "16") (pinfunction "INT2_16") (pintype "bidirectional"))
    )
    (net (code "115") (name "unconnected-(U$10-INT3-Pad23)") (class "Default")
      (node (ref "U$10") (pin "23") (pinfunction "INT3_23") (pintype "bidirectional"))
    )
    (net (code "116") (name "unconnected-(U$11-INT-Pad2)") (class "Default")
      (node (ref "U$11") (pin "2") (pinfunction "INT_2") (pintype "bidirectional"))
    )
    (net (code "117") (name "unconnected-(U$11-INT1-Pad9)") (class "Default")
      (node (ref "U$11") (pin "9") (pinfunction "INT1_9") (pintype "bidirectional"))
    )
    (net (code "118") (name "unconnected-(U$11-INT2-Pad16)") (class "Default")
      (node (ref "U$11") (pin "16") (pinfunction "INT2_16") (pintype "bidirectional"))
    )
    (net (code "119") (name "unconnected-(U$11-INT3-Pad23)") (class "Default")
      (node (ref "U$11") (pin "23") (pinfunction "INT3_23") (pintype "bidirectional"))
    )
    (net (code "120") (name "unconnected-(U$12-INT-Pad2)") (class "Default")
      (node (ref "U$12") (pin "2") (pinfunction "INT_2") (pintype "bidirectional"))
    )
    (net (code "121") (name "unconnected-(U$12-INT1-Pad9)") (class "Default")
      (node (ref "U$12") (pin "9") (pinfunction "INT1_9") (pintype "bidirectional"))
    )
    (net (code "122") (name "unconnected-(U$12-INT2-Pad16)") (class "Default")
      (node (ref "U$12") (pin "16") (pinfunction "INT2_16") (pintype "bidirectional"))
    )
    (net (code "123") (name "unconnected-(U$12-INT3-Pad23)") (class "Default")
      (node (ref "U$12") (pin "23") (pinfunction "INT3_23") (pintype "bidirectional"))
    )
    (net (code "124") (name "unconnected-(U$13-INT-Pad2)") (class "Default")
      (node (ref "U$13") (pin "2") (pinfunction "INT_2") (pintype "bidirectional"))
    )
    (net (code "125") (name "unconnected-(U$13-INT1-Pad9)") (class "Default")
      (node (ref "U$13") (pin "9") (pinfunction "INT1_9") (pintype "bidirectional"))
    )
    (net (code "126") (name "unconnected-(U$13-INT2-Pad16)") (class "Default")
      (node (ref "U$13") (pin "16") (pinfunction "INT2_16") (pintype "bidirectional"))
    )
    (net (code "127") (name "unconnected-(U$13-INT3-Pad23)") (class "Default")
      (node (ref "U$13") (pin "23") (pinfunction "INT3_23") (pintype "bidirectional"))
    )
    (net (code "128") (name "unconnected-(U$14-INT-Pad2)") (class "Default")
      (node (ref "U$14") (pin "2") (pinfunction "INT_2") (pintype "bidirectional"))
    )
    (net (code "129") (name "unconnected-(U$14-INT1-Pad9)") (class "Default")
      (node (ref "U$14") (pin "9") (pinfunction "INT1_9") (pintype "bidirectional"))
    )
    (net (code "130") (name "unconnected-(U$14-INT2-Pad16)") (class "Default")
      (node (ref "U$14") (pin "16") (pinfunction "INT2_16") (pintype "bidirectional"))
    )
    (net (code "131") (name "unconnected-(U$14-INT3-Pad23)") (class "Default")
      (node (ref "U$14") (pin "23") (pinfunction "INT3_23") (pintype "bidirectional"))
    )
    (net (code "132") (name "unconnected-(U$15-INT-Pad2)") (class "Default")
      (node (ref "U$15") (pin "2") (pinfunction "INT_2") (pintype "bidirectional"))
    )
    (net (code "133") (name "unconnected-(U$15-INT1-Pad9)") (class "Default")
      (node (ref "U$15") (pin "9") (pinfunction "INT1_9") (pintype "bidirectional"))
    )
    (net (code "134") (name "unconnected-(U$15-INT2-Pad16)") (class "Default")
      (node (ref "U$15") (pin "16") (pinfunction "INT2_16") (pintype "bidirectional"))
    )
    (net (code "135") (name "unconnected-(U$15-INT3-Pad23)") (class "Default")
      (node (ref "U$15") (pin "23") (pinfunction "INT3_23") (pintype "bidirectional"))
    )
    (net (code "136") (name "unconnected-(U$16-INT-Pad2)") (class "Default")
      (node (ref "U$16") (pin "2") (pinfunction "INT_2") (pintype "bidirectional"))
    )
    (net (code "137") (name "unconnected-(U$16-INT1-Pad9)") (class "Default")
      (node (ref "U$16") (pin "9") (pinfunction "INT1_9") (pintype "bidirectional"))
    )
    (net (code "138") (name "unconnected-(U$16-INT2-Pad16)") (class "Default")
      (node (ref "U$16") (pin "16") (pinfunction "INT2_16") (pintype "bidirectional"))
    )
    (net (code "139") (name "unconnected-(U$16-INT3-Pad23)") (class "Default")
      (node (ref "U$16") (pin "23") (pinfunction "INT3_23") (pintype "bidirectional"))
    )
    (net (code "140") (name "unconnected-(U$17-INT-Pad2)") (class "Default")
      (node (ref "U$17") (pin "2") (pinfunction "INT_2") (pintype "bidirectional"))
    )
    (net (code "141") (name "unconnected-(U$17-INT1-Pad9)") (class "Default")
      (node (ref "U$17") (pin "9") (pinfunction "INT1_9") (pintype "bidirectional"))
    )
    (net (code "142") (name "unconnected-(U$17-INT2-Pad16)") (class "Default")
      (node (ref "U$17") (pin "16") (pinfunction "INT2_16") (pintype "bidirectional"))
    )
    (net (code "143") (name "unconnected-(U$17-INT3-Pad23)") (class "Default")
      (node (ref "U$17") (pin "23") (pinfunction "INT3_23") (pintype "bidirectional"))
    )
    (net (code "144") (name "unconnected-(U$18-INT-Pad2)") (class "Default")
      (node (ref "U$18") (pin "2") (pinfunction "INT_2") (pintype "bidirectional"))
    )
    (net (code "145") (name "unconnected-(U$18-INT1-Pad9)") (class "Default")
      (node (ref "U$18") (pin "9") (pinfunction "INT1_9") (pintype "bidirectional"))
    )
    (net (code "146") (name "unconnected-(U$18-INT2-Pad16)") (class "Default")
      (node (ref "U$18") (pin "16") (pinfunction "INT2_16") (pintype "bidirectional"))
    )
    (net (code "147") (name "unconnected-(U$18-INT3-Pad23)") (class "Default")
      (node (ref "U$18") (pin "23") (pinfunction "INT3_23") (pintype "bidirectional"))
    )
    (net (code "148") (name "unconnected-(U$19-INT-Pad2)") (class "Default")
      (node (ref "U$19") (pin "2") (pinfunction "INT_2") (pintype "bidirectional"))
    )
    (net (code "149") (name "unconnected-(U$19-INT1-Pad9)") (class "Default")
      (node (ref "U$19") (pin "9") (pinfunction "INT1_9") (pintype "bidirectional"))
    )
    (net (code "150") (name "unconnected-(U$19-INT2-Pad16)") (class "Default")
      (node (ref "U$19") (pin "16") (pinfunction "INT2_16") (pintype "bidirectional"))
    )
    (net (code "151") (name "unconnected-(U$19-INT3-Pad23)") (class "Default")
      (node (ref "U$19") (pin "23") (pinfunction "INT3_23") (pintype "bidirectional"))
    )
    (net (code "152") (name "unconnected-(U$20-INT-Pad2)") (class "Default")
      (node (ref "U$20") (pin "2") (pinfunction "INT_2") (pintype "bidirectional"))
    )
    (net (code "153") (name "unconnected-(U$20-INT1-Pad9)") (class "Default")
      (node (ref "U$20") (pin "9") (pinfunction "INT1_9") (pintype "bidirectional"))
    )
    (net (code "154") (name "unconnected-(U$20-INT2-Pad16)") (class "Default")
      (node (ref "U$20") (pin "16") (pinfunction "INT2_16") (pintype "bidirectional"))
    )
    (net (code "155") (name "unconnected-(U$20-INT3-Pad23)") (class "Default")
      (node (ref "U$20") (pin "23") (pinfunction "INT3_23") (pintype "bidirectional"))
    )
    (net (code "156") (name "unconnected-(U$21-INT-Pad2)") (class "Default")
      (node (ref "U$21") (pin "2") (pinfunction "INT_2") (pintype "bidirectional"))
    )
    (net (code "157") (name "unconnected-(U$21-INT1-Pad9)") (class "Default")
      (node (ref "U$21") (pin "9") (pinfunction "INT1_9") (pintype "bidirectional"))
    )
    (net (code "158") (name "unconnected-(U$21-INT2-Pad16)") (class "Default")
      (node (ref "U$21") (pin "16") (pinfunction "INT2_16") (pintype "bidirectional"))
    )
    (net (code "159") (name "unconnected-(U$21-INT3-Pad23)") (class "Default")
      (node (ref "U$21") (pin "23") (pinfunction "INT3_23") (pintype "bidirectional"))
    )
    (net (code "160") (name "unconnected-(U$22-INT-Pad2)") (class "Default")
      (node (ref "U$22") (pin "2") (pinfunction "INT_2") (pintype "bidirectional"))
    )
    (net (code "161") (name "unconnected-(U$22-INT1-Pad9)") (class "Default")
      (node (ref "U$22") (pin "9") (pinfunction "INT1_9") (pintype "bidirectional"))
    )
    (net (code "162") (name "unconnected-(U$22-INT2-Pad16)") (class "Default")
      (node (ref "U$22") (pin "16") (pinfunction "INT2_16") (pintype "bidirectional"))
    )
    (net (code "163") (name "unconnected-(U$22-INT3-Pad23)") (class "Default")
      (node (ref "U$22") (pin "23") (pinfunction "INT3_23") (pintype "bidirectional"))
    )
    (net (code "164") (name "unconnected-(U$23-INT-Pad2)") (class "Default")
      (node (ref "U$23") (pin "2") (pinfunction "INT_2") (pintype "bidirectional"))
    )
    (net (code "165") (name "unconnected-(U$23-INT1-Pad9)") (class "Default")
      (node (ref "U$23") (pin "9") (pinfunction "INT1_9") (pintype "bidirectional"))
    )
    (net (code "166") (name "unconnected-(U$23-INT2-Pad16)") (class "Default")
      (node (ref "U$23") (pin "16") (pinfunction "INT2_16") (pintype "bidirectional"))
    )
    (net (code "167") (name "unconnected-(U$23-INT3-Pad23)") (class "Default")
      (node (ref "U$23") (pin "23") (pinfunction "INT3_23") (pintype "bidirectional"))
    )
    (net (code "168") (name "unconnected-(U$24-INT-Pad2)") (class "Default")
      (node (ref "U$24") (pin "2") (pinfunction "INT_2") (pintype "bidirectional"))
    )
    (net (code "169") (name "unconnected-(U$24-INT1-Pad9)") (class "Default")
      (node (ref "U$24") (pin "9") (pinfunction "INT1_9") (pintype "bidirectional"))
    )
    (net (code "170") (name "unconnected-(U$24-INT2-Pad16)") (class "Default")
      (node (ref "U$24") (pin "16") (pinfunction "INT2_16") (pintype "bidirectional"))
    )
    (net (code "171") (name "unconnected-(U$24-INT3-Pad23)") (class "Default")
      (node (ref "U$24") (pin "23") (pinfunction "INT3_23") (pintype "bidirectional"))
    )
    (net (code "172") (name "unconnected-(U$25-P$2-Pad2)") (class "Default")
      (node (ref "U$25") (pin "2") (pinfunction "P$2_2") (pintype "bidirectional"))
    )
    (net (code "173") (name "unconnected-(U$26-NIC-Pad41)") (class "Default")
      (node (ref "U$26") (pin "41") (pinfunction "NIC_41") (pintype "bidirectional"))
    )
    (net (code "174") (name "unconnected-(U$26-NIC-Pad42)") (class "Default")
      (node (ref "U$26") (pin "42") (pinfunction "NIC_42") (pintype "bidirectional"))
    )
    (net (code "175") (name "unconnected-(U$26-NIC-Pad44)") (class "Default")
      (node (ref "U$26") (pin "44") (pinfunction "NIC_44") (pintype "bidirectional"))
    )
    (net (code "176") (name "unconnected-(U$26-S13-Pad48)") (class "Default")
      (node (ref "U$26") (pin "48") (pinfunction "S13_48") (pintype "bidirectional"))
    )
    (net (code "177") (name "unconnected-(U$26-S14-Pad47)") (class "Default")
      (node (ref "U$26") (pin "47") (pinfunction "S14_47") (pintype "bidirectional"))
    )
    (net (code "178") (name "unconnected-(U$26-S15-Pad46)") (class "Default")
      (node (ref "U$26") (pin "46") (pinfunction "S15_46") (pintype "bidirectional"))
    )
    (net (code "179") (name "unconnected-(U$26-S16-Pad45)") (class "Default")
      (node (ref "U$26") (pin "45") (pinfunction "S16_45") (pintype "bidirectional"))
    )
    (net (code "180") (name "unconnected-(U$26-S29-Pad37)") (class "Default")
      (node (ref "U$26") (pin "37") (pinfunction "S29_37") (pintype "bidirectional"))
    )
    (net (code "181") (name "unconnected-(U$26-S30-Pad38)") (class "Default")
      (node (ref "U$26") (pin "38") (pinfunction "S30_38") (pintype "bidirectional"))
    )
    (net (code "182") (name "unconnected-(U$26-S31-Pad39)") (class "Default")
      (node (ref "U$26") (pin "39") (pinfunction "S31_39") (pintype "bidirectional"))
    )
    (net (code "183") (name "unconnected-(U$26-S32-Pad40)") (class "Default")
      (node (ref "U$26") (pin "40") (pinfunction "S32_40") (pintype "bidirectional"))
    )
    (net (code "184") (name "unconnected-(U$27-NIC-Pad41)") (class "Default")
      (node (ref "U$27") (pin "41") (pinfunction "NIC_41") (pintype "bidirectional"))
    )
    (net (code "185") (name "unconnected-(U$27-NIC-Pad42)") (class "Default")
      (node (ref "U$27") (pin "42") (pinfunction "NIC_42") (pintype "bidirectional"))
    )
    (net (code "186") (name "unconnected-(U$27-NIC-Pad44)") (class "Default")
      (node (ref "U$27") (pin "44") (pinfunction "NIC_44") (pintype "bidirectional"))
    )
    (net (code "187") (name "unconnected-(U$27-S13-Pad48)") (class "Default")
      (node (ref "U$27") (pin "48") (pinfunction "S13_48") (pintype "bidirectional"))
    )
    (net (code "188") (name "unconnected-(U$27-S14-Pad47)") (class "Default")
      (node (ref "U$27") (pin "47") (pinfunction "S14_47") (pintype "bidirectional"))
    )
    (net (code "189") (name "unconnected-(U$27-S15-Pad46)") (class "Default")
      (node (ref "U$27") (pin "46") (pinfunction "S15_46") (pintype "bidirectional"))
    )
    (net (code "190") (name "unconnected-(U$27-S16-Pad45)") (class "Default")
      (node (ref "U$27") (pin "45") (pinfunction "S16_45") (pintype "bidirectional"))
    )
    (net (code "191") (name "unconnected-(U$27-S29-Pad37)") (class "Default")
      (node (ref "U$27") (pin "37") (pinfunction "S29_37") (pintype "bidirectional"))
    )
    (net (code "192") (name "unconnected-(U$27-S30-Pad38)") (class "Default")
      (node (ref "U$27") (pin "38") (pinfunction "S30_38") (pintype "bidirectional"))
    )
    (net (code "193") (name "unconnected-(U$27-S31-Pad39)") (class "Default")
      (node (ref "U$27") (pin "39") (pinfunction "S31_39") (pintype "bidirectional"))
    )
    (net (code "194") (name "unconnected-(U$27-S32-Pad40)") (class "Default")
      (node (ref "U$27") (pin "40") (pinfunction "S32_40") (pintype "bidirectional"))
    )
  )
)
